# Module_DIO.net
KiCad netlist of a schematic drawn in EAGLE
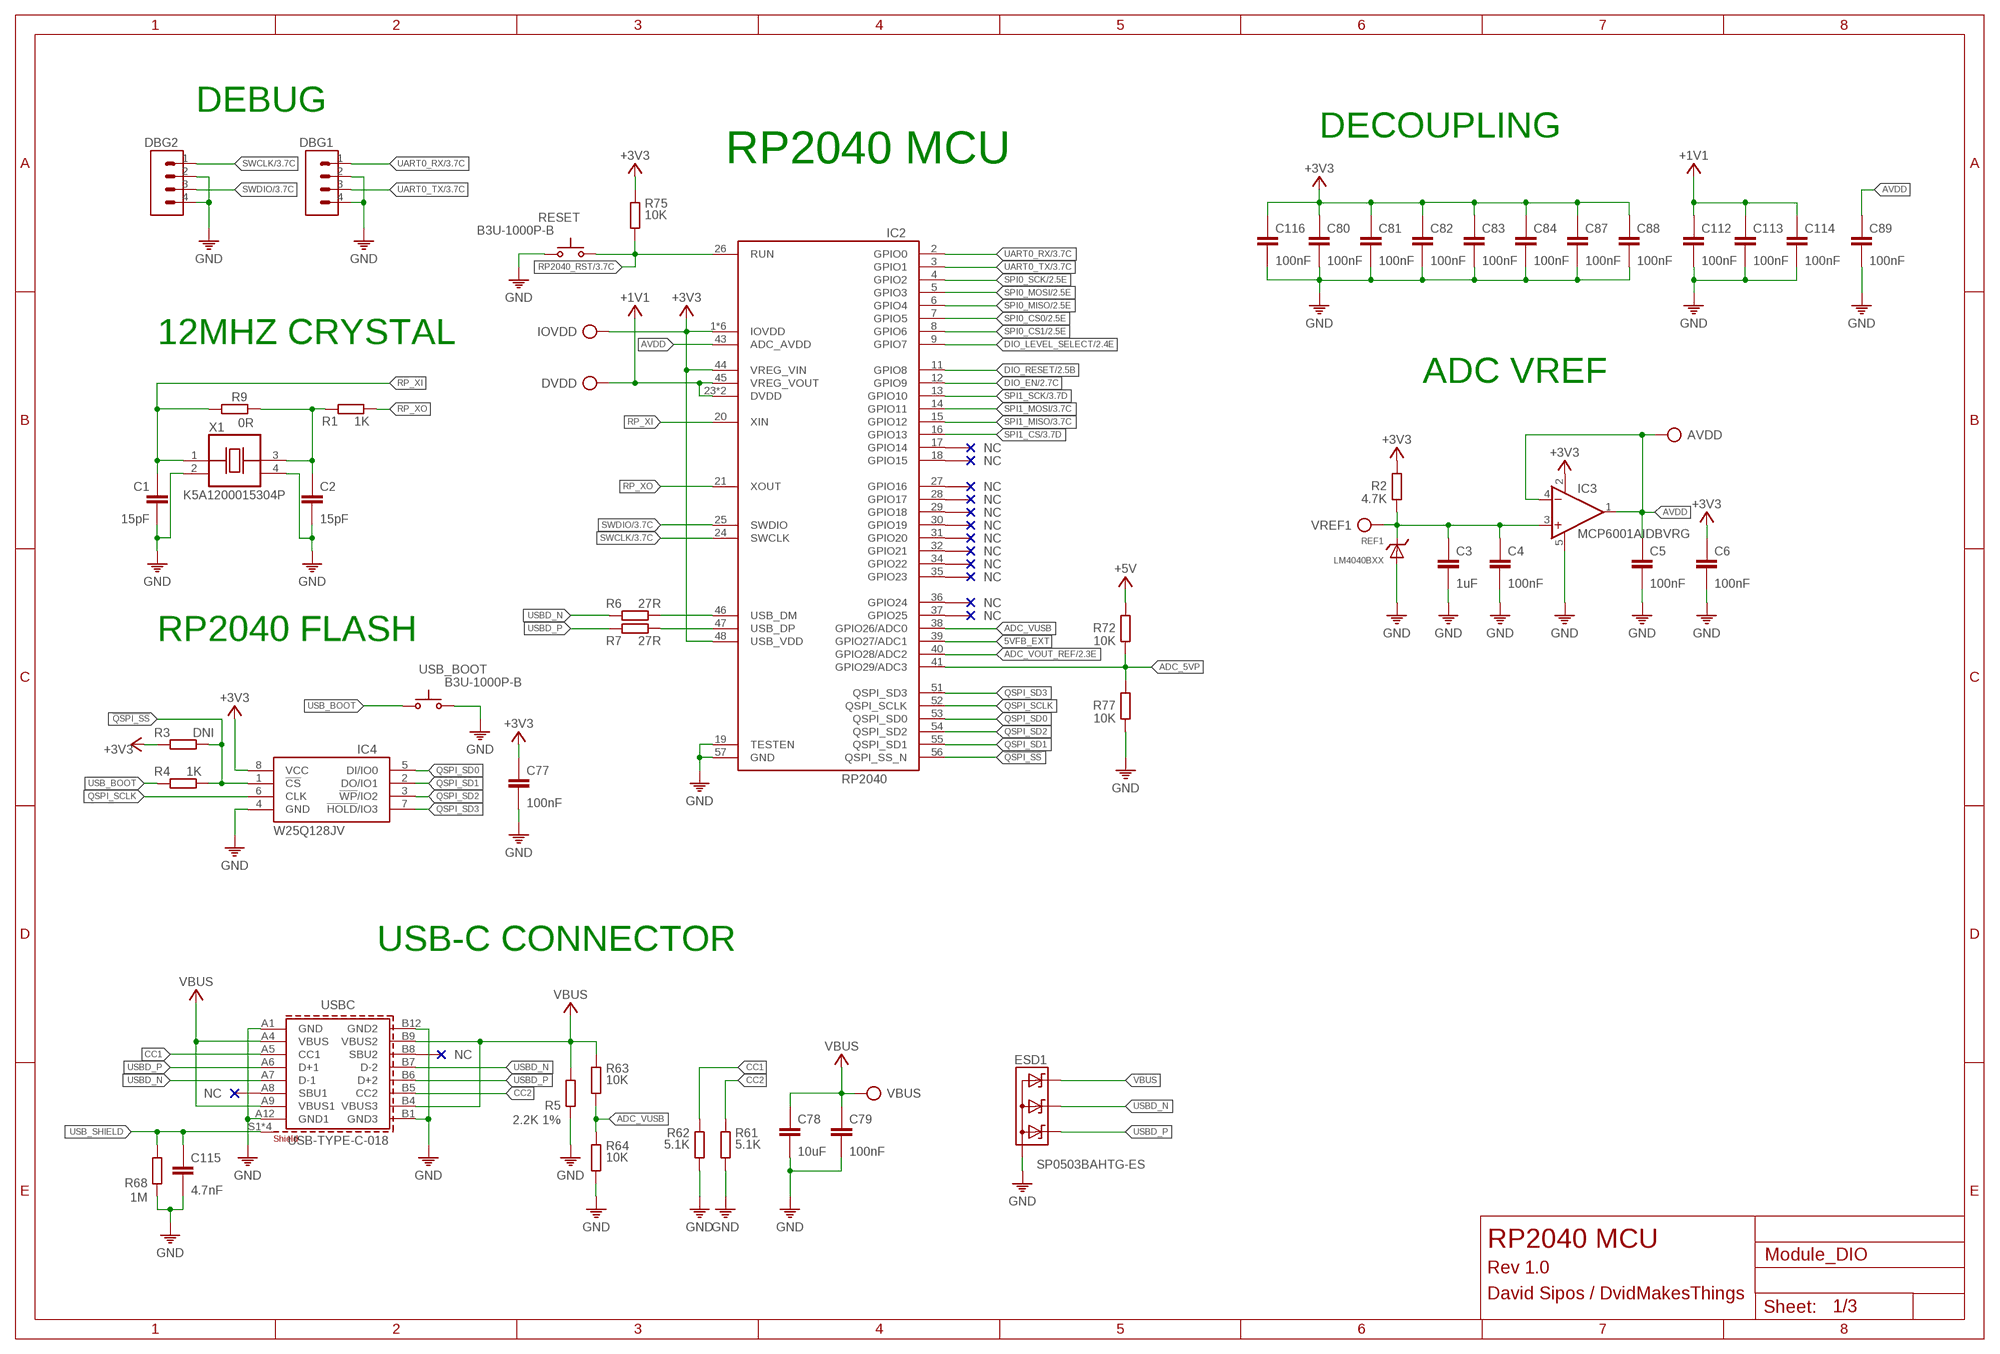
[diagram p0: schematic, sheet 1]
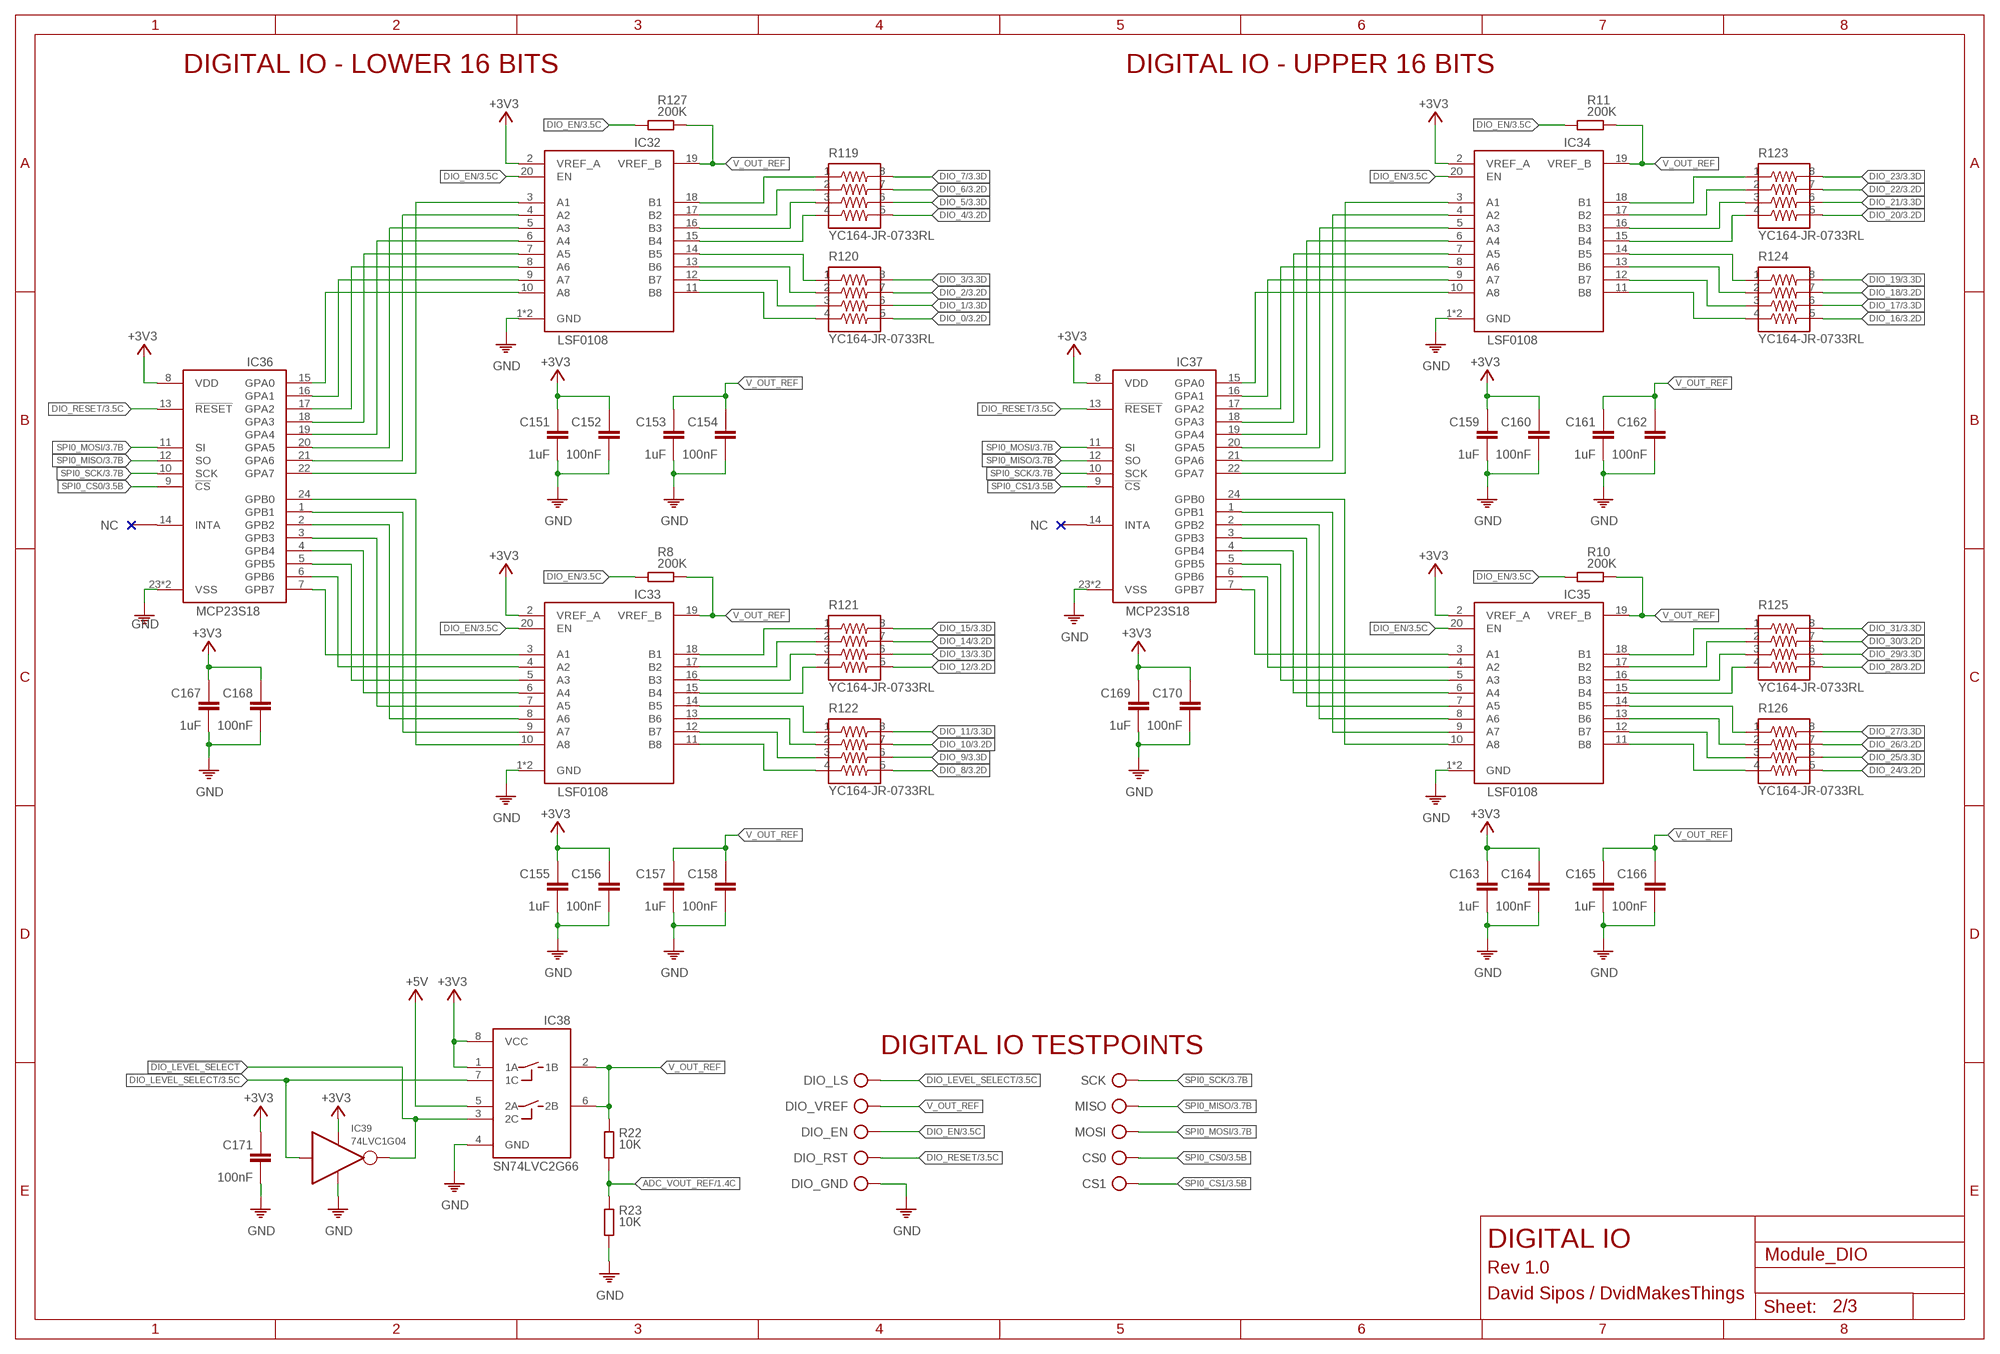
[diagram p1: schematic, sheet 2]
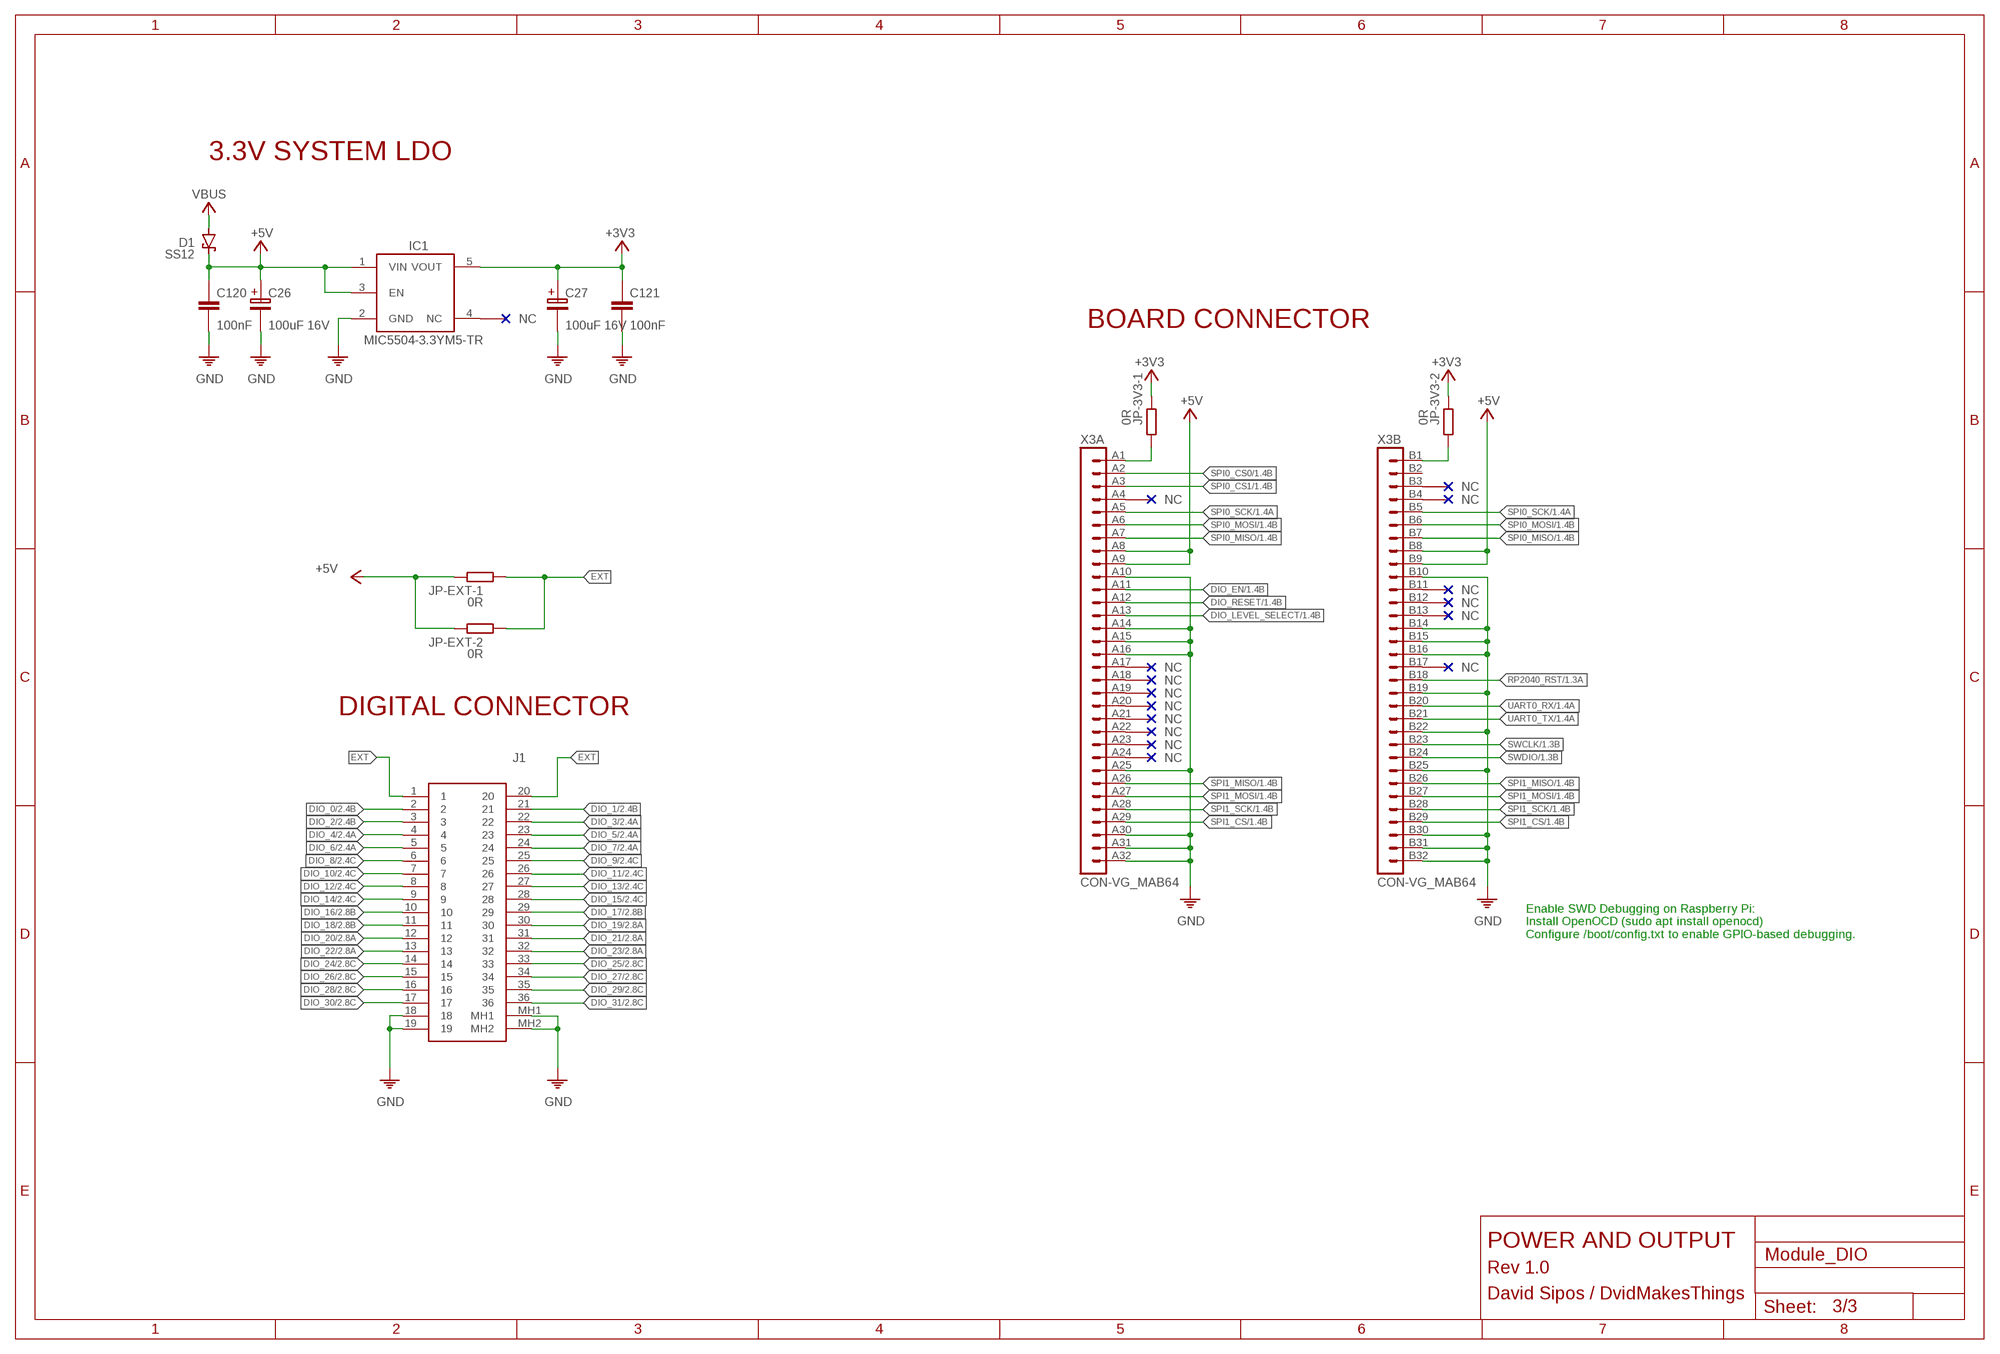
[diagram p2: schematic, sheet 3]

(export (version "E")
  (design (tool "Eeschema 10.0.6"))
  (components
    (comp (ref "AVDD")
      (value "TP")
      (footprint "eagle-import:TP")
      (libsource (lib "eagle-import") (part "TP"))
    )
    (comp (ref "C1")
      (value "15pF")
      (footprint "eagle-import:C0402")
      (libsource (lib "eagle-import") (part "C-0402"))
    )
    (comp (ref "C2")
      (value "15pF")
      (footprint "eagle-import:C0402")
      (libsource (lib "eagle-import") (part "C-0402"))
    )
    (comp (ref "C3")
      (value "1uF")
      (footprint "eagle-import:C0402")
      (libsource (lib "eagle-import") (part "C-0402"))
    )
    (comp (ref "C4")
      (value "100nF")
      (footprint "eagle-import:C0402")
      (libsource (lib "eagle-import") (part "C-0402"))
    )
    (comp (ref "C5")
      (value "100nF")
      (footprint "eagle-import:C0402")
      (libsource (lib "eagle-import") (part "C-0402"))
    )
    (comp (ref "C6")
      (value "100nF")
      (footprint "eagle-import:C0402")
      (libsource (lib "eagle-import") (part "C-0402"))
    )
    (comp (ref "C77")
      (value "100nF")
      (footprint "eagle-import:C0402")
      (libsource (lib "eagle-import") (part "C-0402"))
    )
    (comp (ref "C78")
      (value "10uF")
      (footprint "eagle-import:0805")
      (libsource (lib "eagle-import") (part "C0805"))
    )
    (comp (ref "C79")
      (value "100nF")
      (footprint "eagle-import:0402")
      (libsource (lib "eagle-import") (part "C0402"))
    )
    (comp (ref "C80")
      (value "100nF")
      (footprint "eagle-import:C0402")
      (libsource (lib "eagle-import") (part "C-0402"))
    )
    (comp (ref "C81")
      (value "100nF")
      (footprint "eagle-import:C0402")
      (libsource (lib "eagle-import") (part "C-0402"))
    )
    (comp (ref "C82")
      (value "100nF")
      (footprint "eagle-import:C0402")
      (libsource (lib "eagle-import") (part "C-0402"))
    )
    (comp (ref "C83")
      (value "100nF")
      (footprint "eagle-import:C0402")
      (libsource (lib "eagle-import") (part "C-0402"))
    )
    (comp (ref "C84")
      (value "100nF")
      (footprint "eagle-import:C0402")
      (libsource (lib "eagle-import") (part "C-0402"))
    )
    (comp (ref "C87")
      (value "100nF")
      (footprint "eagle-import:C0402")
      (libsource (lib "eagle-import") (part "C-0402"))
    )
    (comp (ref "C88")
      (value "100nF")
      (footprint "eagle-import:C0402")
      (libsource (lib "eagle-import") (part "C-0402"))
    )
    (comp (ref "C89")
      (value "100nF")
      (footprint "eagle-import:C0402")
      (libsource (lib "eagle-import") (part "C-0402"))
    )
    (comp (ref "C112")
      (value "100nF")
      (footprint "eagle-import:C0402")
      (libsource (lib "eagle-import") (part "C-0402"))
    )
    (comp (ref "C113")
      (value "100nF")
      (footprint "eagle-import:C0402")
      (libsource (lib "eagle-import") (part "C-0402"))
    )
    (comp (ref "C114")
      (value "100nF")
      (footprint "eagle-import:C0402")
      (libsource (lib "eagle-import") (part "C-0402"))
    )
    (comp (ref "C115")
      (value "4.7nF")
      (footprint "eagle-import:0402")
      (libsource (lib "eagle-import") (part "C0402"))
    )
    (comp (ref "C116")
      (value "100nF")
      (footprint "eagle-import:C0402")
      (libsource (lib "eagle-import") (part "C-0402"))
    )
    (comp (ref "DBG1")
      (value "CON-1X4")
      (footprint "eagle-import:1X4")
      (libsource (lib "eagle-import") (part "CON-1X4"))
    )
    (comp (ref "DBG2")
      (value "CON-1X4")
      (footprint "eagle-import:1X4")
      (libsource (lib "eagle-import") (part "CON-1X4"))
    )
    (comp (ref "DVDD")
      (value "TP")
      (footprint "eagle-import:TP")
      (libsource (lib "eagle-import") (part "TP"))
    )
    (comp (ref "ESD1")
      (value "SP0503BAHTG-ES")
      (footprint "eagle-import:SOT143")
      (libsource (lib "eagle-import") (part "SP0503BAHT"))
    )
    (comp (ref "IC2")
      (value "RP2040")
      (footprint "eagle-import:QFN40P700X700X100-57T510")
      (libsource (lib "eagle-import") (part "RP2040"))
    )
    (comp (ref "IC3")
      (value "MCP6001AIDBVRG")
      (footprint "eagle-import:SOT23-5")
      (libsource (lib "eagle-import") (part "MCP6001RT"))
    )
    (comp (ref "IC4")
      (value "W25Q128JVPIQ")
      (footprint "eagle-import:SON127P600X500X75-8N")
      (libsource (lib "eagle-import") (part "W25Q128JVP"))
    )
    (comp (ref "IOVDD")
      (value "TP")
      (footprint "eagle-import:TP")
      (libsource (lib "eagle-import") (part "TP"))
    )
    (comp (ref "R1")
      (value "1K")
      (footprint "eagle-import:0402")
      (libsource (lib "eagle-import") (part "R0402"))
    )
    (comp (ref "R2")
      (value "4.7K")
      (footprint "eagle-import:0402")
      (libsource (lib "eagle-import") (part "R0402"))
    )
    (comp (ref "R3")
      (value "DNI")
      (footprint "eagle-import:0402")
      (libsource (lib "eagle-import") (part "R0402"))
    )
    (comp (ref "R4")
      (value "1K")
      (footprint "eagle-import:0402")
      (libsource (lib "eagle-import") (part "R0402"))
    )
    (comp (ref "R5")
      (value "2.2K 1%")
      (footprint "eagle-import:0402")
      (libsource (lib "eagle-import") (part "ds_passive_46685041_R0402"))
    )
    (comp (ref "R6")
      (value "27R")
      (footprint "eagle-import:0402")
      (libsource (lib "eagle-import") (part "R0402"))
    )
    (comp (ref "R7")
      (value "27R")
      (footprint "eagle-import:0402")
      (libsource (lib "eagle-import") (part "R0402"))
    )
    (comp (ref "R9")
      (value "0R")
      (footprint "eagle-import:0402")
      (libsource (lib "eagle-import") (part "R0402"))
    )
    (comp (ref "R61")
      (value "5.1K")
      (footprint "eagle-import:0402")
      (libsource (lib "eagle-import") (part "ds_passive_46685041_R0402"))
    )
    (comp (ref "R62")
      (value "5.1K")
      (footprint "eagle-import:0402")
      (libsource (lib "eagle-import") (part "ds_passive_46685041_R0402"))
    )
    (comp (ref "R63")
      (value "10K")
      (footprint "eagle-import:0402")
      (libsource (lib "eagle-import") (part "ds_passive_46685041_R0402"))
    )
    (comp (ref "R64")
      (value "10K")
      (footprint "eagle-import:0402")
      (libsource (lib "eagle-import") (part "ds_passive_46685041_R0402"))
    )
    (comp (ref "R68")
      (value "1M")
      (footprint "eagle-import:0402")
      (libsource (lib "eagle-import") (part "ds_passive_46685041_R0402"))
    )
    (comp (ref "R72")
      (value "10K")
      (footprint "eagle-import:0402")
      (libsource (lib "eagle-import") (part "R0402"))
    )
    (comp (ref "R75")
      (value "10K")
      (footprint "eagle-import:0402")
      (libsource (lib "eagle-import") (part "ds_passive_46685041_R0402"))
    )
    (comp (ref "R77")
      (value "10K")
      (footprint "eagle-import:0402")
      (libsource (lib "eagle-import") (part "R0402"))
    )
    (comp (ref "REF1")
      (value "LM4040BXX")
      (footprint "eagle-import:SOT23")
      (libsource (lib "eagle-import") (part "LM4040BXX"))
    )
    (comp (ref "RESET")
      (value "B3U-1000P-B")
      (footprint "eagle-import:SWITCH-OMRON_B3U-1000P")
      (libsource (lib "eagle-import") (part "SWITCH-OMRON_B3U-1000P"))
    )
    (comp (ref "USBC")
      (value "USB-TYPE-C-018")
      (footprint "eagle-import:629722000214")
      (libsource (lib "eagle-import") (part "629722000214"))
    )
    (comp (ref "USB_BOOT")
      (value "B3U-1000P-B")
      (footprint "eagle-import:SWITCH-OMRON_B3U-1000P")
      (libsource (lib "eagle-import") (part "SWITCH-OMRON_B3U-1000P"))
    )
    (comp (ref "VBUS")
      (value "TP")
      (footprint "eagle-import:TP")
      (libsource (lib "eagle-import") (part "TP"))
    )
    (comp (ref "VREF1")
      (value "TP")
      (footprint "eagle-import:TP")
      (libsource (lib "eagle-import") (part "TP"))
    )
    (comp (ref "X1")
      (value "K5A1200015304P")
      (footprint "eagle-import:OSCCC500X320X130")
      (libsource (lib "eagle-import") (part "CRYSTAL"))
    )
    (comp (ref "C26")
      (value "100uF 16V")
      (footprint "eagle-import:100UF-16V")
      (libsource (lib "eagle-import") (part "CPOL"))
    )
    (comp (ref "C27")
      (value "100uF 16V")
      (footprint "eagle-import:100UF-16V")
      (libsource (lib "eagle-import") (part "CPOL"))
    )
    (comp (ref "C120")
      (value "100nF")
      (footprint "eagle-import:C0402")
      (libsource (lib "eagle-import") (part "C-0402"))
    )
    (comp (ref "C121")
      (value "100nF")
      (footprint "eagle-import:C0402")
      (libsource (lib "eagle-import") (part "C-0402"))
    )
    (comp (ref "D1")
      (value "SS12")
      (footprint "eagle-import:SMA")
      (fields
        (field (name "DIGIKEY_PART_NUMBER") "SS12FSCT-ND")
        (field (name "MANUFACTURER") "ON Semiconductor")
        (field (name "CREATED_BY") "PCBLayout.com")
      )
      (libsource (lib "eagle-import") (part "SS12"))
    )
    (comp (ref "IC1")
      (value "MIC5504-3.3YM5-TR")
      (footprint "eagle-import:SOT23-5")
      (libsource (lib "eagle-import") (part "MIC5504-3.3YM5-TR"))
    )
    (comp (ref "J1")
      (value "N10236-52B3PC")
      (footprint "eagle-import:MDB36")
      (libsource (lib "eagle-import") (part "N10236-52B3PC"))
    )
    (comp (ref "JP-3V3-1")
      (value "0R")
      (footprint "eagle-import:0603")
      (libsource (lib "eagle-import") (part "R0603"))
    )
    (comp (ref "JP-3V3-2")
      (value "0R")
      (footprint "eagle-import:0603")
      (libsource (lib "eagle-import") (part "R0603"))
    )
    (comp (ref "JP-EXT-1")
      (value "0R")
      (footprint "eagle-import:0603")
      (libsource (lib "eagle-import") (part "R0603"))
    )
    (comp (ref "JP-EXT-2")
      (value "0R")
      (footprint "eagle-import:0603")
      (libsource (lib "eagle-import") (part "R0603"))
    )
    (comp (ref "X3")
      (value "CON-VG_MAB64")
      (footprint "eagle-import:CON-VG_MAB64")
      (libsource (lib "eagle-import") (part "CON-VG_MAB64"))
    )
    (comp (ref "C151")
      (value "1uF")
      (footprint "eagle-import:C0402")
      (libsource (lib "eagle-import") (part "C-0402"))
    )
    (comp (ref "C152")
      (value "100nF")
      (footprint "eagle-import:C0402")
      (libsource (lib "eagle-import") (part "C-0402"))
    )
    (comp (ref "C153")
      (value "1uF")
      (footprint "eagle-import:C0402")
      (libsource (lib "eagle-import") (part "C-0402"))
    )
    (comp (ref "C154")
      (value "100nF")
      (footprint "eagle-import:C0402")
      (libsource (lib "eagle-import") (part "C-0402"))
    )
    (comp (ref "C155")
      (value "1uF")
      (footprint "eagle-import:C0402")
      (libsource (lib "eagle-import") (part "C-0402"))
    )
    (comp (ref "C156")
      (value "100nF")
      (footprint "eagle-import:C0402")
      (libsource (lib "eagle-import") (part "C-0402"))
    )
    (comp (ref "C157")
      (value "1uF")
      (footprint "eagle-import:C0402")
      (libsource (lib "eagle-import") (part "C-0402"))
    )
    (comp (ref "C158")
      (value "100nF")
      (footprint "eagle-import:C0402")
      (libsource (lib "eagle-import") (part "C-0402"))
    )
    (comp (ref "C159")
      (value "1uF")
      (footprint "eagle-import:C0402")
      (libsource (lib "eagle-import") (part "C-0402"))
    )
    (comp (ref "C160")
      (value "100nF")
      (footprint "eagle-import:C0402")
      (libsource (lib "eagle-import") (part "C-0402"))
    )
    (comp (ref "C161")
      (value "1uF")
      (footprint "eagle-import:C0402")
      (libsource (lib "eagle-import") (part "C-0402"))
    )
    (comp (ref "C162")
      (value "100nF")
      (footprint "eagle-import:C0402")
      (libsource (lib "eagle-import") (part "C-0402"))
    )
    (comp (ref "C163")
      (value "1uF")
      (footprint "eagle-import:C0402")
      (libsource (lib "eagle-import") (part "C-0402"))
    )
    (comp (ref "C164")
      (value "100nF")
      (footprint "eagle-import:C0402")
      (libsource (lib "eagle-import") (part "C-0402"))
    )
    (comp (ref "C165")
      (value "1uF")
      (footprint "eagle-import:C0402")
      (libsource (lib "eagle-import") (part "C-0402"))
    )
    (comp (ref "C166")
      (value "100nF")
      (footprint "eagle-import:C0402")
      (libsource (lib "eagle-import") (part "C-0402"))
    )
    (comp (ref "C167")
      (value "1uF")
      (footprint "eagle-import:C0402")
      (libsource (lib "eagle-import") (part "C-0402"))
    )
    (comp (ref "C168")
      (value "100nF")
      (footprint "eagle-import:C0402")
      (libsource (lib "eagle-import") (part "C-0402"))
    )
    (comp (ref "C169")
      (value "1uF")
      (footprint "eagle-import:C0402")
      (libsource (lib "eagle-import") (part "C-0402"))
    )
    (comp (ref "C170")
      (value "100nF")
      (footprint "eagle-import:C0402")
      (libsource (lib "eagle-import") (part "C-0402"))
    )
    (comp (ref "C171")
      (value "100nF")
      (footprint "eagle-import:C0603")
      (libsource (lib "eagle-import") (part "C-0603"))
    )
    (comp (ref "CS0") (value "TP") (footprint "eagle-import:TP") (libsource (lib "eagle-import") (part "TP")))
    (comp (ref "CS1") (value "TP") (footprint "eagle-import:TP") (libsource (lib "eagle-import") (part "TP")))
    (comp (ref "DIO_EN")
      (value "TP")
      (footprint "eagle-import:TP")
      (libsource (lib "eagle-import") (part "TP"))
    )
    (comp (ref "DIO_GND")
      (value "TP")
      (footprint "eagle-import:TP")
      (libsource (lib "eagle-import") (part "TP"))
    )
    (comp (ref "DIO_LS")
      (value "TP")
      (footprint "eagle-import:TP")
      (libsource (lib "eagle-import") (part "TP"))
    )
    (comp (ref "DIO_RST")
      (value "TP")
      (footprint "eagle-import:TP")
      (libsource (lib "eagle-import") (part "TP"))
    )
    (comp (ref "DIO_VREF")
      (value "TP")
      (footprint "eagle-import:TP")
      (libsource (lib "eagle-import") (part "TP"))
    )
    (comp (ref "IC32")
      (value "LSF0108")
      (footprint "eagle-import:VQFN20")
      (libsource (lib "eagle-import") (part "LSF0108-Q1"))
    )
    (comp (ref "IC33")
      (value "LSF0108")
      (footprint "eagle-import:VQFN20")
      (libsource (lib "eagle-import") (part "LSF0108-Q1"))
    )
    (comp (ref "IC34")
      (value "LSF0108")
      (footprint "eagle-import:VQFN20")
      (libsource (lib "eagle-import") (part "LSF0108-Q1"))
    )
    (comp (ref "IC35")
      (value "LSF0108")
      (footprint "eagle-import:VQFN20")
      (libsource (lib "eagle-import") (part "LSF0108-Q1"))
    )
    (comp (ref "IC36")
      (value "MCP23S18")
      (footprint "eagle-import:QFN50P400X400X100-25T265")
      (libsource (lib "eagle-import") (part "MCP23S18"))
    )
    (comp (ref "IC37")
      (value "MCP23S18")
      (footprint "eagle-import:QFN50P400X400X100-25T265")
      (libsource (lib "eagle-import") (part "MCP23S18"))
    )
    (comp (ref "IC38")
      (value "SN74LVC2G66")
      (footprint "eagle-import:SOP50P310X90-8N")
      (libsource (lib "eagle-import") (part "SN74LVC2G66"))
    )
    (comp (ref "IC39")
      (value "74LVC1G04")
      (footprint "eagle-import:SOT95P280X145-5N")
      (libsource (lib "eagle-import") (part "74LVC1G04"))
    )
    (comp (ref "MISO")
      (value "TP")
      (footprint "eagle-import:TP")
      (libsource (lib "eagle-import") (part "TP"))
    )
    (comp (ref "MOSI")
      (value "TP")
      (footprint "eagle-import:TP")
      (libsource (lib "eagle-import") (part "TP"))
    )
    (comp (ref "R8")
      (value "200K")
      (footprint "eagle-import:0402")
      (libsource (lib "eagle-import") (part "R0402"))
    )
    (comp (ref "R10")
      (value "200K")
      (footprint "eagle-import:0402")
      (libsource (lib "eagle-import") (part "R0402"))
    )
    (comp (ref "R11")
      (value "200K")
      (footprint "eagle-import:0402")
      (libsource (lib "eagle-import") (part "R0402"))
    )
    (comp (ref "R22")
      (value "10K")
      (footprint "eagle-import:0402")
      (libsource (lib "eagle-import") (part "R0402"))
    )
    (comp (ref "R23")
      (value "10K")
      (footprint "eagle-import:0402")
      (libsource (lib "eagle-import") (part "R0402"))
    )
    (comp (ref "R119")
      (value "YC164-JR-0733RL")
      (footprint "eagle-import:YC164-JR-0733RL")
      (fields (field (name "MANUFACTURER") "Yageo") (field (name "CREATED_BY") "PCBLayout.com"))
      (libsource (lib "eagle-import") (part "YC164-JR-0733RL"))
    )
    (comp (ref "R120")
      (value "YC164-JR-0733RL")
      (footprint "eagle-import:YC164-JR-0733RL")
      (fields (field (name "MANUFACTURER") "Yageo") (field (name "CREATED_BY") "PCBLayout.com"))
      (libsource (lib "eagle-import") (part "YC164-JR-0733RL"))
    )
    (comp (ref "R121")
      (value "YC164-JR-0733RL")
      (footprint "eagle-import:YC164-JR-0733RL")
      (fields (field (name "MANUFACTURER") "Yageo") (field (name "CREATED_BY") "PCBLayout.com"))
      (libsource (lib "eagle-import") (part "YC164-JR-0733RL"))
    )
    (comp (ref "R122")
      (value "YC164-JR-0733RL")
      (footprint "eagle-import:YC164-JR-0733RL")
      (fields (field (name "MANUFACTURER") "Yageo") (field (name "CREATED_BY") "PCBLayout.com"))
      (libsource (lib "eagle-import") (part "YC164-JR-0733RL"))
    )
    (comp (ref "R123")
      (value "YC164-JR-0733RL")
      (footprint "eagle-import:YC164-JR-0733RL")
      (fields (field (name "MANUFACTURER") "Yageo") (field (name "CREATED_BY") "PCBLayout.com"))
      (libsource (lib "eagle-import") (part "YC164-JR-0733RL"))
    )
    (comp (ref "R124")
      (value "YC164-JR-0733RL")
      (footprint "eagle-import:YC164-JR-0733RL")
      (fields (field (name "MANUFACTURER") "Yageo") (field (name "CREATED_BY") "PCBLayout.com"))
      (libsource (lib "eagle-import") (part "YC164-JR-0733RL"))
    )
    (comp (ref "R125")
      (value "YC164-JR-0733RL")
      (footprint "eagle-import:YC164-JR-0733RL")
      (fields (field (name "MANUFACTURER") "Yageo") (field (name "CREATED_BY") "PCBLayout.com"))
      (libsource (lib "eagle-import") (part "YC164-JR-0733RL"))
    )
    (comp (ref "R126")
      (value "YC164-JR-0733RL")
      (footprint "eagle-import:YC164-JR-0733RL")
      (fields (field (name "MANUFACTURER") "Yageo") (field (name "CREATED_BY") "PCBLayout.com"))
      (libsource (lib "eagle-import") (part "YC164-JR-0733RL"))
    )
    (comp (ref "R127")
      (value "200K")
      (footprint "eagle-import:0402")
      (libsource (lib "eagle-import") (part "R0402"))
    )
    (comp (ref "SCK") (value "TP") (footprint "eagle-import:TP") (libsource (lib "eagle-import") (part "TP")))
  )
  (nets
    (net (code "1") (name "+1V1") (class "Default")
      (node (ref "C112") (pin "1") (pinfunction "1_1") (pintype "passive"))
      (node (ref "C113") (pin "1") (pinfunction "1_1") (pintype "passive"))
      (node (ref "C114") (pin "1") (pinfunction "1_1") (pintype "passive"))
      (node (ref "DVDD") (pin "TP") (pinfunction "P$1_TP") (pintype "bidirectional"))
      (node (ref "IC2") (pin "23") (pinfunction "DVDD_23") (pintype "bidirectional"))
      (node (ref "IC2") (pin "45") (pinfunction "VREG_VOUT_45") (pintype "bidirectional"))
      (node (ref "IC2") (pin "50") (pinfunction "DVDD_50") (pintype "bidirectional"))
    )
    (net (code "2") (name "+3V3") (class "Default")
      (node (ref "C116") (pin "1") (pinfunction "1_1") (pintype "passive"))
      (node (ref "C121") (pin "1") (pinfunction "1_1") (pintype "passive"))
      (node (ref "C151") (pin "1") (pinfunction "1_1") (pintype "passive"))
      (node (ref "C152") (pin "1") (pinfunction "1_1") (pintype "passive"))
      (node (ref "C155") (pin "1") (pinfunction "1_1") (pintype "passive"))
      (node (ref "C156") (pin "1") (pinfunction "1_1") (pintype "passive"))
      (node (ref "C159") (pin "1") (pinfunction "1_1") (pintype "passive"))
      (node (ref "C160") (pin "1") (pinfunction "1_1") (pintype "passive"))
      (node (ref "C163") (pin "1") (pinfunction "1_1") (pintype "passive"))
      (node (ref "C164") (pin "1") (pinfunction "1_1") (pintype "passive"))
      (node (ref "C167") (pin "1") (pinfunction "1_1") (pintype "passive"))
      (node (ref "C168") (pin "1") (pinfunction "1_1") (pintype "passive"))
      (node (ref "C169") (pin "1") (pinfunction "1_1") (pintype "passive"))
      (node (ref "C170") (pin "1") (pinfunction "1_1") (pintype "passive"))
      (node (ref "C171") (pin "1") (pinfunction "1_1") (pintype "passive"))
      (node (ref "C27") (pin "1") (pinfunction "1_1") (pintype "passive"))
      (node (ref "C6") (pin "1") (pinfunction "1_1") (pintype "passive"))
      (node (ref "C77") (pin "1") (pinfunction "1_1") (pintype "passive"))
      (node (ref "C80") (pin "1") (pinfunction "1_1") (pintype "passive"))
      (node (ref "C81") (pin "1") (pinfunction "1_1") (pintype "passive"))
      (node (ref "C82") (pin "1") (pinfunction "1_1") (pintype "passive"))
      (node (ref "C83") (pin "1") (pinfunction "1_1") (pintype "passive"))
      (node (ref "C84") (pin "1") (pinfunction "1_1") (pintype "passive"))
      (node (ref "C87") (pin "1") (pinfunction "1_1") (pintype "passive"))
      (node (ref "C88") (pin "1") (pinfunction "1_1") (pintype "passive"))
      (node (ref "IC1") (pin "5") (pinfunction "VOUT_5") (pintype "bidirectional"))
      (node (ref "IC2") (pin "1") (pinfunction "IOVDD_1") (pintype "bidirectional"))
      (node (ref "IC2") (pin "10") (pinfunction "IOVDD_10") (pintype "bidirectional"))
      (node (ref "IC2") (pin "22") (pinfunction "IOVDD_22") (pintype "bidirectional"))
      (node (ref "IC2") (pin "33") (pinfunction "IOVDD_33") (pintype "bidirectional"))
      (node (ref "IC2") (pin "42") (pinfunction "IOVDD_42") (pintype "bidirectional"))
      (node (ref "IC2") (pin "44") (pinfunction "VREG_VIN_44") (pintype "bidirectional"))
      (node (ref "IC2") (pin "48") (pinfunction "USB_VDD_48") (pintype "bidirectional"))
      (node (ref "IC2") (pin "49") (pinfunction "IOVDD_49") (pintype "bidirectional"))
      (node (ref "IC3") (pin "2") (pinfunction "V+_2") (pintype "power_in"))
      (node (ref "IC32") (pin "2") (pinfunction "VREF_A_2") (pintype "power_in"))
      (node (ref "IC33") (pin "2") (pinfunction "VREF_A_2") (pintype "power_in"))
      (node (ref "IC34") (pin "2") (pinfunction "VREF_A_2") (pintype "power_in"))
      (node (ref "IC35") (pin "2") (pinfunction "VREF_A_2") (pintype "power_in"))
      (node (ref "IC36") (pin "8") (pinfunction "VDD_8") (pintype "power_in"))
      (node (ref "IC37") (pin "8") (pinfunction "VDD_8") (pintype "power_in"))
      (node (ref "IC38") (pin "1") (pinfunction "1A_1") (pintype "bidirectional"))
      (node (ref "IC38") (pin "8") (pinfunction "VCC_8") (pintype "power_in"))
      (node (ref "IC39") (pin "5") (pinfunction "V+_5") (pintype "bidirectional"))
      (node (ref "IC4") (pin "8") (pinfunction "VCC_8") (pintype "power_in"))
      (node (ref "IOVDD") (pin "TP") (pinfunction "P$1_TP") (pintype "bidirectional"))
      (node (ref "JP-3V3-1") (pin "1") (pinfunction "1_1") (pintype "passive"))
      (node (ref "JP-3V3-2") (pin "1") (pinfunction "1_1") (pintype "passive"))
      (node (ref "R2") (pin "2") (pinfunction "2_2") (pintype "passive"))
      (node (ref "R3") (pin "2") (pinfunction "2_2") (pintype "passive"))
      (node (ref "R75") (pin "1") (pinfunction "1_1") (pintype "passive"))
    )
    (net (code "3") (name "+5V") (class "Default")
      (node (ref "C120") (pin "1") (pinfunction "1_1") (pintype "passive"))
      (node (ref "C26") (pin "1") (pinfunction "1_1") (pintype "passive"))
      (node (ref "D1") (pin "C") (pinfunction "C_C") (pintype "passive"))
      (node (ref "IC1") (pin "1") (pinfunction "VIN_1") (pintype "bidirectional"))
      (node (ref "IC1") (pin "3") (pinfunction "EN_3") (pintype "bidirectional"))
      (node (ref "IC38") (pin "5") (pinfunction "2A_5") (pintype "bidirectional"))
      (node (ref "JP-EXT-1") (pin "1") (pinfunction "1_1") (pintype "passive"))
      (node (ref "JP-EXT-2") (pin "1") (pinfunction "1_1") (pintype "passive"))
      (node (ref "R72") (pin "2") (pinfunction "2_2") (pintype "passive"))
      (node (ref "X3") (pin "A8") (pinfunction "8_A8") (pintype "passive"))
      (node (ref "X3") (pin "A9") (pinfunction "9_A9") (pintype "passive"))
      (node (ref "X3") (pin "B8") (pinfunction "8_B8") (pintype "passive"))
      (node (ref "X3") (pin "B9") (pinfunction "9_B9") (pintype "passive"))
    )
    (net (code "4") (name "5VFB_EXT") (class "Default")
      (node (ref "IC2") (pin "39") (pinfunction "GPIO27/ADC1_39") (pintype "bidirectional"))
    )
    (net (code "5") (name "ADC_5VP") (class "Default")
      (node (ref "IC2") (pin "41") (pinfunction "GPIO29/ADC3_41") (pintype "bidirectional"))
      (node (ref "R72") (pin "1") (pinfunction "1_1") (pintype "passive"))
      (node (ref "R77") (pin "2") (pinfunction "2_2") (pintype "passive"))
    )
    (net (code "6") (name "ADC_VOUT_REF") (class "Default")
      (node (ref "IC2") (pin "40") (pinfunction "GPIO28/ADC2_40") (pintype "bidirectional"))
      (node (ref "R22") (pin "2") (pinfunction "2_2") (pintype "passive"))
      (node (ref "R23") (pin "1") (pinfunction "1_1") (pintype "passive"))
    )
    (net (code "7") (name "ADC_VUSB") (class "Default")
      (node (ref "IC2") (pin "38") (pinfunction "GPIO26/ADC0_38") (pintype "bidirectional"))
      (node (ref "R63") (pin "2") (pinfunction "2_2") (pintype "passive"))
      (node (ref "R64") (pin "1") (pinfunction "1_1") (pintype "passive"))
    )
    (net (code "8") (name "AVDD") (class "Default")
      (node (ref "AVDD") (pin "TP") (pinfunction "P$1_TP") (pintype "bidirectional"))
      (node (ref "C5") (pin "1") (pinfunction "1_1") (pintype "passive"))
      (node (ref "C89") (pin "1") (pinfunction "1_1") (pintype "passive"))
      (node (ref "IC2") (pin "43") (pinfunction "ADC_AVDD_43") (pintype "bidirectional"))
      (node (ref "IC3") (pin "1") (pinfunction "OUT_1") (pintype "output"))
      (node (ref "IC3") (pin "4") (pinfunction "-IN_4") (pintype "input"))
    )
    (net (code "9") (name "CC1") (class "Default")
      (node (ref "R62") (pin "1") (pinfunction "1_1") (pintype "passive"))
      (node (ref "USBC") (pin "A5") (pinfunction "CC1_A5") (pintype "passive"))
    )
    (net (code "10") (name "CC2") (class "Default")
      (node (ref "R61") (pin "1") (pinfunction "1_1") (pintype "passive"))
      (node (ref "USBC") (pin "B5") (pinfunction "CC2_B5") (pintype "passive"))
    )
    (net (code "11") (name "DIO_0") (class "Default")
      (node (ref "J1") (pin "2") (pinfunction "2_2") (pintype "bidirectional"))
      (node (ref "R120") (pin "5") (pinfunction "5_5") (pintype "passive"))
    )
    (net (code "12") (name "DIO_1") (class "Default")
      (node (ref "J1") (pin "21") (pinfunction "21_21") (pintype "bidirectional"))
      (node (ref "R120") (pin "6") (pinfunction "6_6") (pintype "passive"))
    )
    (net (code "13") (name "DIO_2") (class "Default")
      (node (ref "J1") (pin "3") (pinfunction "3_3") (pintype "bidirectional"))
      (node (ref "R120") (pin "7") (pinfunction "7_7") (pintype "passive"))
    )
    (net (code "14") (name "DIO_3") (class "Default")
      (node (ref "J1") (pin "22") (pinfunction "22_22") (pintype "bidirectional"))
      (node (ref "R120") (pin "8") (pinfunction "8_8") (pintype "passive"))
    )
    (net (code "15") (name "DIO_4") (class "Default")
      (node (ref "J1") (pin "4") (pinfunction "4_4") (pintype "bidirectional"))
      (node (ref "R119") (pin "5") (pinfunction "5_5") (pintype "passive"))
    )
    (net (code "16") (name "DIO_5") (class "Default")
      (node (ref "J1") (pin "23") (pinfunction "23_23") (pintype "bidirectional"))
      (node (ref "R119") (pin "6") (pinfunction "6_6") (pintype "passive"))
    )
    (net (code "17") (name "DIO_6") (class "Default")
      (node (ref "J1") (pin "5") (pinfunction "5_5") (pintype "bidirectional"))
      (node (ref "R119") (pin "7") (pinfunction "7_7") (pintype "passive"))
    )
    (net (code "18") (name "DIO_7") (class "Default")
      (node (ref "J1") (pin "24") (pinfunction "24_24") (pintype "bidirectional"))
      (node (ref "R119") (pin "8") (pinfunction "8_8") (pintype "passive"))
    )
    (net (code "19") (name "DIO_8") (class "Default")
      (node (ref "J1") (pin "6") (pinfunction "6_6") (pintype "bidirectional"))
      (node (ref "R122") (pin "5") (pinfunction "5_5") (pintype "passive"))
    )
    (net (code "20") (name "DIO_9") (class "Default")
      (node (ref "J1") (pin "25") (pinfunction "25_25") (pintype "bidirectional"))
      (node (ref "R122") (pin "6") (pinfunction "6_6") (pintype "passive"))
    )
    (net (code "21") (name "DIO_10") (class "Default")
      (node (ref "J1") (pin "7") (pinfunction "7_7") (pintype "bidirectional"))
      (node (ref "R122") (pin "7") (pinfunction "7_7") (pintype "passive"))
    )
    (net (code "22") (name "DIO_11") (class "Default")
      (node (ref "J1") (pin "26") (pinfunction "26_26") (pintype "bidirectional"))
      (node (ref "R122") (pin "8") (pinfunction "8_8") (pintype "passive"))
    )
    (net (code "23") (name "DIO_12") (class "Default")
      (node (ref "J1") (pin "8") (pinfunction "8_8") (pintype "bidirectional"))
      (node (ref "R121") (pin "5") (pinfunction "5_5") (pintype "passive"))
    )
    (net (code "24") (name "DIO_13") (class "Default")
      (node (ref "J1") (pin "27") (pinfunction "27_27") (pintype "bidirectional"))
      (node (ref "R121") (pin "6") (pinfunction "6_6") (pintype "passive"))
    )
    (net (code "25") (name "DIO_14") (class "Default")
      (node (ref "J1") (pin "9") (pinfunction "9_9") (pintype "bidirectional"))
      (node (ref "R121") (pin "7") (pinfunction "7_7") (pintype "passive"))
    )
    (net (code "26") (name "DIO_15") (class "Default")
      (node (ref "J1") (pin "28") (pinfunction "28_28") (pintype "bidirectional"))
      (node (ref "R121") (pin "8") (pinfunction "8_8") (pintype "passive"))
    )
    (net (code "27") (name "DIO_16") (class "Default")
      (node (ref "J1") (pin "10") (pinfunction "10_10") (pintype "bidirectional"))
      (node (ref "R124") (pin "5") (pinfunction "5_5") (pintype "passive"))
    )
    (net (code "28") (name "DIO_17") (class "Default")
      (node (ref "J1") (pin "29") (pinfunction "29_29") (pintype "bidirectional"))
      (node (ref "R124") (pin "6") (pinfunction "6_6") (pintype "passive"))
    )
    (net (code "29") (name "DIO_18") (class "Default")
      (node (ref "J1") (pin "11") (pinfunction "11_11") (pintype "bidirectional"))
      (node (ref "R124") (pin "7") (pinfunction "7_7") (pintype "passive"))
    )
    (net (code "30") (name "DIO_19") (class "Default")
      (node (ref "J1") (pin "30") (pinfunction "30_30") (pintype "bidirectional"))
      (node (ref "R124") (pin "8") (pinfunction "8_8") (pintype "passive"))
    )
    (net (code "31") (name "DIO_20") (class "Default")
      (node (ref "J1") (pin "12") (pinfunction "12_12") (pintype "bidirectional"))
      (node (ref "R123") (pin "5") (pinfunction "5_5") (pintype "passive"))
    )
    (net (code "32") (name "DIO_21") (class "Default")
      (node (ref "J1") (pin "31") (pinfunction "31_31") (pintype "bidirectional"))
      (node (ref "R123") (pin "6") (pinfunction "6_6") (pintype "passive"))
    )
    (net (code "33") (name "DIO_22") (class "Default")
      (node (ref "J1") (pin "13") (pinfunction "13_13") (pintype "bidirectional"))
      (node (ref "R123") (pin "7") (pinfunction "7_7") (pintype "passive"))
    )
    (net (code "34") (name "DIO_23") (class "Default")
      (node (ref "J1") (pin "32") (pinfunction "32_32") (pintype "bidirectional"))
      (node (ref "R123") (pin "8") (pinfunction "8_8") (pintype "passive"))
    )
    (net (code "35") (name "DIO_24") (class "Default")
      (node (ref "J1") (pin "14") (pinfunction "14_14") (pintype "bidirectional"))
      (node (ref "R126") (pin "5") (pinfunction "5_5") (pintype "passive"))
    )
    (net (code "36") (name "DIO_25") (class "Default")
      (node (ref "J1") (pin "33") (pinfunction "33_33") (pintype "bidirectional"))
      (node (ref "R126") (pin "6") (pinfunction "6_6") (pintype "passive"))
    )
    (net (code "37") (name "DIO_26") (class "Default")
      (node (ref "J1") (pin "15") (pinfunction "15_15") (pintype "bidirectional"))
      (node (ref "R126") (pin "7") (pinfunction "7_7") (pintype "passive"))
    )
    (net (code "38") (name "DIO_27") (class "Default")
      (node (ref "J1") (pin "34") (pinfunction "34_34") (pintype "bidirectional"))
      (node (ref "R126") (pin "8") (pinfunction "8_8") (pintype "passive"))
    )
    (net (code "39") (name "DIO_28") (class "Default")
      (node (ref "J1") (pin "16") (pinfunction "16_16") (pintype "bidirectional"))
      (node (ref "R125") (pin "5") (pinfunction "5_5") (pintype "passive"))
    )
    (net (code "40") (name "DIO_29") (class "Default")
      (node (ref "J1") (pin "35") (pinfunction "35_35") (pintype "bidirectional"))
      (node (ref "R125") (pin "6") (pinfunction "6_6") (pintype "passive"))
    )
    (net (code "41") (name "DIO_30") (class "Default")
      (node (ref "J1") (pin "17") (pinfunction "17_17") (pintype "bidirectional"))
      (node (ref "R125") (pin "7") (pinfunction "7_7") (pintype "passive"))
    )
    (net (code "42") (name "DIO_31") (class "Default")
      (node (ref "J1") (pin "36") (pinfunction "36_36") (pintype "bidirectional"))
      (node (ref "R125") (pin "8") (pinfunction "8_8") (pintype "passive"))
    )
    (net (code "43") (name "DIO_EN") (class "Default")
      (node (ref "DIO_EN") (pin "TP") (pinfunction "P$1_TP") (pintype "bidirectional"))
      (node (ref "IC2") (pin "12") (pinfunction "GPIO9_12") (pintype "bidirectional"))
      (node (ref "IC32") (pin "20") (pinfunction "EN_20") (pintype "bidirectional"))
      (node (ref "IC33") (pin "20") (pinfunction "EN_20") (pintype "bidirectional"))
      (node (ref "IC34") (pin "20") (pinfunction "EN_20") (pintype "bidirectional"))
      (node (ref "IC35") (pin "20") (pinfunction "EN_20") (pintype "bidirectional"))
      (node (ref "R10") (pin "2") (pinfunction "2_2") (pintype "passive"))
      (node (ref "R11") (pin "2") (pinfunction "2_2") (pintype "passive"))
      (node (ref "R127") (pin "2") (pinfunction "2_2") (pintype "passive"))
      (node (ref "R8") (pin "2") (pinfunction "2_2") (pintype "passive"))
      (node (ref "X3") (pin "A11") (pinfunction "11_A11") (pintype "passive"))
    )
    (net (code "44") (name "DIO_LEVEL_SELECT") (class "Default")
      (node (ref "DIO_LS") (pin "TP") (pinfunction "P$1_TP") (pintype "bidirectional"))
      (node (ref "IC2") (pin "9") (pinfunction "GPIO7_9") (pintype "bidirectional"))
      (node (ref "IC38") (pin "7") (pinfunction "1C_7") (pintype "input"))
      (node (ref "IC39") (pin "2") (pinfunction "IN_2") (pintype "bidirectional"))
      (node (ref "X3") (pin "A13") (pinfunction "13_A13") (pintype "passive"))
    )
    (net (code "45") (name "DIO_RESET") (class "Default")
      (node (ref "DIO_RST") (pin "TP") (pinfunction "P$1_TP") (pintype "bidirectional"))
      (node (ref "IC2") (pin "11") (pinfunction "GPIO8_11") (pintype "bidirectional"))
      (node (ref "IC36") (pin "13") (pinfunction "~{RESET}_13") (pintype "input"))
      (node (ref "IC37") (pin "13") (pinfunction "~{RESET}_13") (pintype "input"))
      (node (ref "X3") (pin "A12") (pinfunction "12_A12") (pintype "passive"))
    )
    (net (code "46") (name "EXT") (class "Default")
      (node (ref "J1") (pin "1") (pinfunction "1_1") (pintype "bidirectional"))
      (node (ref "J1") (pin "20") (pinfunction "20_20") (pintype "bidirectional"))
      (node (ref "JP-EXT-1") (pin "2") (pinfunction "2_2") (pintype "passive"))
      (node (ref "JP-EXT-2") (pin "2") (pinfunction "2_2") (pintype "passive"))
    )
    (net (code "47") (name "GND") (class "Default")
      (node (ref "C1") (pin "2") (pinfunction "2_2") (pintype "passive"))
      (node (ref "C112") (pin "2") (pinfunction "2_2") (pintype "passive"))
      (node (ref "C113") (pin "2") (pinfunction "2_2") (pintype "passive"))
      (node (ref "C114") (pin "2") (pinfunction "2_2") (pintype "passive"))
      (node (ref "C115") (pin "2") (pinfunction "2_2") (pintype "passive"))
      (node (ref "C116") (pin "2") (pinfunction "2_2") (pintype "passive"))
      (node (ref "C120") (pin "2") (pinfunction "2_2") (pintype "passive"))
      (node (ref "C121") (pin "2") (pinfunction "2_2") (pintype "passive"))
      (node (ref "C151") (pin "2") (pinfunction "2_2") (pintype "passive"))
      (node (ref "C152") (pin "2") (pinfunction "2_2") (pintype "passive"))
      (node (ref "C153") (pin "2") (pinfunction "2_2") (pintype "passive"))
      (node (ref "C154") (pin "2") (pinfunction "2_2") (pintype "passive"))
      (node (ref "C155") (pin "2") (pinfunction "2_2") (pintype "passive"))
      (node (ref "C156") (pin "2") (pinfunction "2_2") (pintype "passive"))
      (node (ref "C157") (pin "2") (pinfunction "2_2") (pintype "passive"))
      (node (ref "C158") (pin "2") (pinfunction "2_2") (pintype "passive"))
      (node (ref "C159") (pin "2") (pinfunction "2_2") (pintype "passive"))
      (node (ref "C160") (pin "2") (pinfunction "2_2") (pintype "passive"))
      (node (ref "C161") (pin "2") (pinfunction "2_2") (pintype "passive"))
      (node (ref "C162") (pin "2") (pinfunction "2_2") (pintype "passive"))
      (node (ref "C163") (pin "2") (pinfunction "2_2") (pintype "passive"))
      (node (ref "C164") (pin "2") (pinfunction "2_2") (pintype "passive"))
      (node (ref "C165") (pin "2") (pinfunction "2_2") (pintype "passive"))
      (node (ref "C166") (pin "2") (pinfunction "2_2") (pintype "passive"))
      (node (ref "C167") (pin "2") (pinfunction "2_2") (pintype "passive"))
      (node (ref "C168") (pin "2") (pinfunction "2_2") (pintype "passive"))
      (node (ref "C169") (pin "2") (pinfunction "2_2") (pintype "passive"))
      (node (ref "C170") (pin "2") (pinfunction "2_2") (pintype "passive"))
      (node (ref "C171") (pin "2") (pinfunction "2_2") (pintype "passive"))
      (node (ref "C2") (pin "2") (pinfunction "2_2") (pintype "passive"))
      (node (ref "C26") (pin "2") (pinfunction "2_2") (pintype "passive"))
      (node (ref "C27") (pin "2") (pinfunction "2_2") (pintype "passive"))
      (node (ref "C3") (pin "2") (pinfunction "2_2") (pintype "passive"))
      (node (ref "C4") (pin "2") (pinfunction "2_2") (pintype "passive"))
      (node (ref "C5") (pin "2") (pinfunction "2_2") (pintype "passive"))
      (node (ref "C6") (pin "2") (pinfunction "2_2") (pintype "passive"))
      (node (ref "C77") (pin "2") (pinfunction "2_2") (pintype "passive"))
      (node (ref "C78") (pin "2") (pinfunction "2_2") (pintype "passive"))
      (node (ref "C79") (pin "2") (pinfunction "2_2") (pintype "passive"))
      (node (ref "C80") (pin "2") (pinfunction "2_2") (pintype "passive"))
      (node (ref "C81") (pin "2") (pinfunction "2_2") (pintype "passive"))
      (node (ref "C82") (pin "2") (pinfunction "2_2") (pintype "passive"))
      (node (ref "C83") (pin "2") (pinfunction "2_2") (pintype "passive"))
      (node (ref "C84") (pin "2") (pinfunction "2_2") (pintype "passive"))
      (node (ref "C87") (pin "2") (pinfunction "2_2") (pintype "passive"))
      (node (ref "C88") (pin "2") (pinfunction "2_2") (pintype "passive"))
      (node (ref "C89") (pin "2") (pinfunction "2_2") (pintype "passive"))
      (node (ref "DBG1") (pin "2") (pinfunction "P$2_2") (pintype "bidirectional"))
      (node (ref "DBG1") (pin "4") (pinfunction "P$4_4") (pintype "bidirectional"))
      (node (ref "DBG2") (pin "2") (pinfunction "P$2_2") (pintype "bidirectional"))
      (node (ref "DBG2") (pin "4") (pinfunction "P$4_4") (pintype "bidirectional"))
      (node (ref "DIO_GND") (pin "TP") (pinfunction "P$1_TP") (pintype "bidirectional"))
      (node (ref "ESD1") (pin "1") (pinfunction "A_1") (pintype "bidirectional"))
      (node (ref "IC1") (pin "2") (pinfunction "GND_2") (pintype "bidirectional"))
      (node (ref "IC2") (pin "19") (pinfunction "TESTEN_19") (pintype "bidirectional"))
      (node (ref "IC2") (pin "57") (pinfunction "GND_57") (pintype "bidirectional"))
      (node (ref "IC3") (pin "5") (pinfunction "V-_5") (pintype "power_in"))
      (node (ref "IC32") (pin "1") (pinfunction "GND_1") (pintype "power_in"))
      (node (ref "IC32") (pin "PAD") (pinfunction "GND_PAD") (pintype "power_in"))
      (node (ref "IC33") (pin "1") (pinfunction "GND_1") (pintype "power_in"))
      (node (ref "IC33") (pin "PAD") (pinfunction "GND_PAD") (pintype "power_in"))
      (node (ref "IC34") (pin "1") (pinfunction "GND_1") (pintype "power_in"))
      (node (ref "IC34") (pin "PAD") (pinfunction "GND_PAD") (pintype "power_in"))
      (node (ref "IC35") (pin "1") (pinfunction "GND_1") (pintype "power_in"))
      (node (ref "IC35") (pin "PAD") (pinfunction "GND_PAD") (pintype "power_in"))
      (node (ref "IC36") (pin "23") (pinfunction "VSS_23") (pintype "power_in"))
      (node (ref "IC36") (pin "25") (pinfunction "VSS_25") (pintype "power_in"))
      (node (ref "IC37") (pin "23") (pinfunction "VSS_23") (pintype "power_in"))
      (node (ref "IC37") (pin "25") (pinfunction "VSS_25") (pintype "power_in"))
      (node (ref "IC38") (pin "4") (pinfunction "GND_4") (pintype "power_in"))
      (node (ref "IC39") (pin "3") (pinfunction "V-_3") (pintype "bidirectional"))
      (node (ref "IC4") (pin "4") (pinfunction "GND_4") (pintype "power_in"))
      (node (ref "J1") (pin "18") (pinfunction "18_18") (pintype "bidirectional"))
      (node (ref "J1") (pin "19") (pinfunction "19_19") (pintype "bidirectional"))
      (node (ref "J1") (pin "MH1") (pinfunction "MH1_MH1") (pintype "bidirectional"))
      (node (ref "J1") (pin "MH2") (pinfunction "MH2_MH2") (pintype "bidirectional"))
      (node (ref "R23") (pin "2") (pinfunction "2_2") (pintype "passive"))
      (node (ref "R5") (pin "2") (pinfunction "2_2") (pintype "passive"))
      (node (ref "R61") (pin "2") (pinfunction "2_2") (pintype "passive"))
      (node (ref "R62") (pin "2") (pinfunction "2_2") (pintype "passive"))
      (node (ref "R64") (pin "2") (pinfunction "2_2") (pintype "passive"))
      (node (ref "R68") (pin "2") (pinfunction "2_2") (pintype "passive"))
      (node (ref "R77") (pin "1") (pinfunction "1_1") (pintype "passive"))
      (node (ref "REF1") (pin "2") (pinfunction "A_2") (pintype "passive"))
      (node (ref "REF1") (pin "3") (pinfunction "A_3") (pintype "passive"))
      (node (ref "RESET") (pin "2") (pinfunction "S_2") (pintype "passive"))
      (node (ref "USBC") (pin "A1") (pinfunction "GND_A1") (pintype "passive"))
      (node (ref "USBC") (pin "A12") (pinfunction "GND1_A12") (pintype "passive"))
      (node (ref "USBC") (pin "B1") (pinfunction "GND3_B1") (pintype "passive"))
      (node (ref "USBC") (pin "B12") (pinfunction "GND2_B12") (pintype "passive"))
      (node (ref "USB_BOOT") (pin "2") (pinfunction "S_2") (pintype "passive"))
      (node (ref "X1") (pin "2") (pinfunction "VSS_2") (pintype "power_in"))
      (node (ref "X1") (pin "4") (pinfunction "VDD_4") (pintype "power_in"))
      (node (ref "X3") (pin "A10") (pinfunction "10_A10") (pintype "passive"))
      (node (ref "X3") (pin "A14") (pinfunction "14_A14") (pintype "passive"))
      (node (ref "X3") (pin "A15") (pinfunction "15_A15") (pintype "passive"))
      (node (ref "X3") (pin "A16") (pinfunction "16_A16") (pintype "passive"))
      (node (ref "X3") (pin "A25") (pinfunction "25_A25") (pintype "passive"))
      (node (ref "X3") (pin "A30") (pinfunction "30_A30") (pintype "passive"))
      (node (ref "X3") (pin "A31") (pinfunction "31_A31") (pintype "passive"))
      (node (ref "X3") (pin "A32") (pinfunction "32_A32") (pintype "passive"))
      (node (ref "X3") (pin "B10") (pinfunction "10_B10") (pintype "passive"))
      (node (ref "X3") (pin "B14") (pinfunction "14_B14") (pintype "passive"))
      (node (ref "X3") (pin "B15") (pinfunction "15_B15") (pintype "passive"))
      (node (ref "X3") (pin "B16") (pinfunction "16_B16") (pintype "passive"))
      (node (ref "X3") (pin "B19") (pinfunction "19_B19") (pintype "passive"))
      (node (ref "X3") (pin "B22") (pinfunction "22_B22") (pintype "passive"))
      (node (ref "X3") (pin "B25") (pinfunction "25_B25") (pintype "passive"))
      (node (ref "X3") (pin "B30") (pinfunction "30_B30") (pintype "passive"))
      (node (ref "X3") (pin "B31") (pinfunction "31_B31") (pintype "passive"))
      (node (ref "X3") (pin "B32") (pinfunction "32_B32") (pintype "passive"))
    )
    (net (code "48") (name "Net-(IC2-USB_DM)") (class "Default")
      (node (ref "IC2") (pin "46") (pinfunction "USB_DM_46") (pintype "bidirectional"))
      (node (ref "R6") (pin "2") (pinfunction "2_2") (pintype "passive"))
    )
    (net (code "49") (name "Net-(IC2-USB_DP)") (class "Default")
      (node (ref "IC2") (pin "47") (pinfunction "USB_DP_47") (pintype "bidirectional"))
      (node (ref "R7") (pin "2") (pinfunction "2_2") (pintype "passive"))
    )
    (net (code "50") (name "Net-(IC3-+IN)") (class "Default")
      (node (ref "C3") (pin "1") (pinfunction "1_1") (pintype "passive"))
      (node (ref "C4") (pin "1") (pinfunction "1_1") (pintype "passive"))
      (node (ref "IC3") (pin "3") (pinfunction "+IN_3") (pintype "input"))
      (node (ref "R2") (pin "1") (pinfunction "1_1") (pintype "passive"))
      (node (ref "REF1") (pin "1") (pinfunction "C_1") (pintype "passive"))
      (node (ref "VREF1") (pin "TP") (pinfunction "P$1_TP") (pintype "bidirectional"))
    )
    (net (code "51") (name "Net-(IC32-A1)") (class "Default")
      (node (ref "IC32") (pin "3") (pinfunction "A1_3") (pintype "bidirectional"))
      (node (ref "IC36") (pin "22") (pinfunction "GPA7_22") (pintype "bidirectional"))
    )
    (net (code "52") (name "Net-(IC32-A2)") (class "Default")
      (node (ref "IC32") (pin "4") (pinfunction "A2_4") (pintype "bidirectional"))
      (node (ref "IC36") (pin "21") (pinfunction "GPA6_21") (pintype "bidirectional"))
    )
    (net (code "53") (name "Net-(IC32-A3)") (class "Default")
      (node (ref "IC32") (pin "5") (pinfunction "A3_5") (pintype "bidirectional"))
      (node (ref "IC36") (pin "20") (pinfunction "GPA5_20") (pintype "bidirectional"))
    )
    (net (code "54") (name "Net-(IC32-A4)") (class "Default")
      (node (ref "IC32") (pin "6") (pinfunction "A4_6") (pintype "bidirectional"))
      (node (ref "IC36") (pin "19") (pinfunction "GPA4_19") (pintype "bidirectional"))
    )
    (net (code "55") (name "Net-(IC32-A5)") (class "Default")
      (node (ref "IC32") (pin "7") (pinfunction "A5_7") (pintype "bidirectional"))
      (node (ref "IC36") (pin "18") (pinfunction "GPA3_18") (pintype "bidirectional"))
    )
    (net (code "56") (name "Net-(IC32-A6)") (class "Default")
      (node (ref "IC32") (pin "8") (pinfunction "A6_8") (pintype "bidirectional"))
      (node (ref "IC36") (pin "17") (pinfunction "GPA2_17") (pintype "bidirectional"))
    )
    (net (code "57") (name "Net-(IC32-A7)") (class "Default")
      (node (ref "IC32") (pin "9") (pinfunction "A7_9") (pintype "bidirectional"))
      (node (ref "IC36") (pin "16") (pinfunction "GPA1_16") (pintype "bidirectional"))
    )
    (net (code "58") (name "Net-(IC32-A8)") (class "Default")
      (node (ref "IC32") (pin "10") (pinfunction "A8_10") (pintype "bidirectional"))
      (node (ref "IC36") (pin "15") (pinfunction "GPA0_15") (pintype "bidirectional"))
    )
    (net (code "59") (name "Net-(IC32-B1)") (class "Default")
      (node (ref "IC32") (pin "18") (pinfunction "B1_18") (pintype "bidirectional"))
      (node (ref "R119") (pin "1") (pinfunction "1_1") (pintype "passive"))
    )
    (net (code "60") (name "Net-(IC32-B2)") (class "Default")
      (node (ref "IC32") (pin "17") (pinfunction "B2_17") (pintype "bidirectional"))
      (node (ref "R119") (pin "2") (pinfunction "2_2") (pintype "passive"))
    )
    (net (code "61") (name "Net-(IC32-B3)") (class "Default")
      (node (ref "IC32") (pin "16") (pinfunction "B3_16") (pintype "bidirectional"))
      (node (ref "R119") (pin "3") (pinfunction "3_3") (pintype "passive"))
    )
    (net (code "62") (name "Net-(IC32-B4)") (class "Default")
      (node (ref "IC32") (pin "15") (pinfunction "B4_15") (pintype "bidirectional"))
      (node (ref "R119") (pin "4") (pinfunction "4_4") (pintype "passive"))
    )
    (net (code "63") (name "Net-(IC32-B5)") (class "Default")
      (node (ref "IC32") (pin "14") (pinfunction "B5_14") (pintype "bidirectional"))
      (node (ref "R120") (pin "1") (pinfunction "1_1") (pintype "passive"))
    )
    (net (code "64") (name "Net-(IC32-B6)") (class "Default")
      (node (ref "IC32") (pin "13") (pinfunction "B6_13") (pintype "bidirectional"))
      (node (ref "R120") (pin "2") (pinfunction "2_2") (pintype "passive"))
    )
    (net (code "65") (name "Net-(IC32-B7)") (class "Default")
      (node (ref "IC32") (pin "12") (pinfunction "B7_12") (pintype "bidirectional"))
      (node (ref "R120") (pin "3") (pinfunction "3_3") (pintype "passive"))
    )
    (net (code "66") (name "Net-(IC32-B8)") (class "Default")
      (node (ref "IC32") (pin "11") (pinfunction "B8_11") (pintype "bidirectional"))
      (node (ref "R120") (pin "4") (pinfunction "4_4") (pintype "passive"))
    )
    (net (code "67") (name "Net-(IC33-A1)") (class "Default")
      (node (ref "IC33") (pin "3") (pinfunction "A1_3") (pintype "bidirectional"))
      (node (ref "IC36") (pin "7") (pinfunction "GPB7_7") (pintype "bidirectional"))
    )
    (net (code "68") (name "Net-(IC33-A2)") (class "Default")
      (node (ref "IC33") (pin "4") (pinfunction "A2_4") (pintype "bidirectional"))
      (node (ref "IC36") (pin "6") (pinfunction "GPB6_6") (pintype "bidirectional"))
    )
    (net (code "69") (name "Net-(IC33-A3)") (class "Default")
      (node (ref "IC33") (pin "5") (pinfunction "A3_5") (pintype "bidirectional"))
      (node (ref "IC36") (pin "5") (pinfunction "GPB5_5") (pintype "bidirectional"))
    )
    (net (code "70") (name "Net-(IC33-A4)") (class "Default")
      (node (ref "IC33") (pin "6") (pinfunction "A4_6") (pintype "bidirectional"))
      (node (ref "IC36") (pin "4") (pinfunction "GPB4_4") (pintype "bidirectional"))
    )
    (net (code "71") (name "Net-(IC33-A5)") (class "Default")
      (node (ref "IC33") (pin "7") (pinfunction "A5_7") (pintype "bidirectional"))
      (node (ref "IC36") (pin "3") (pinfunction "GPB3_3") (pintype "bidirectional"))
    )
    (net (code "72") (name "Net-(IC33-A6)") (class "Default")
      (node (ref "IC33") (pin "8") (pinfunction "A6_8") (pintype "bidirectional"))
      (node (ref "IC36") (pin "2") (pinfunction "GPB2_2") (pintype "bidirectional"))
    )
    (net (code "73") (name "Net-(IC33-A7)") (class "Default")
      (node (ref "IC33") (pin "9") (pinfunction "A7_9") (pintype "bidirectional"))
      (node (ref "IC36") (pin "1") (pinfunction "GPB1_1") (pintype "bidirectional"))
    )
    (net (code "74") (name "Net-(IC33-A8)") (class "Default")
      (node (ref "IC33") (pin "10") (pinfunction "A8_10") (pintype "bidirectional"))
      (node (ref "IC36") (pin "24") (pinfunction "GPB0_24") (pintype "bidirectional"))
    )
    (net (code "75") (name "Net-(IC33-B1)") (class "Default")
      (node (ref "IC33") (pin "18") (pinfunction "B1_18") (pintype "bidirectional"))
      (node (ref "R121") (pin "1") (pinfunction "1_1") (pintype "passive"))
    )
    (net (code "76") (name "Net-(IC33-B2)") (class "Default")
      (node (ref "IC33") (pin "17") (pinfunction "B2_17") (pintype "bidirectional"))
      (node (ref "R121") (pin "2") (pinfunction "2_2") (pintype "passive"))
    )
    (net (code "77") (name "Net-(IC33-B3)") (class "Default")
      (node (ref "IC33") (pin "16") (pinfunction "B3_16") (pintype "bidirectional"))
      (node (ref "R121") (pin "3") (pinfunction "3_3") (pintype "passive"))
    )
    (net (code "78") (name "Net-(IC33-B4)") (class "Default")
      (node (ref "IC33") (pin "15") (pinfunction "B4_15") (pintype "bidirectional"))
      (node (ref "R121") (pin "4") (pinfunction "4_4") (pintype "passive"))
    )
    (net (code "79") (name "Net-(IC33-B5)") (class "Default")
      (node (ref "IC33") (pin "14") (pinfunction "B5_14") (pintype "bidirectional"))
      (node (ref "R122") (pin "1") (pinfunction "1_1") (pintype "passive"))
    )
    (net (code "80") (name "Net-(IC33-B6)") (class "Default")
      (node (ref "IC33") (pin "13") (pinfunction "B6_13") (pintype "bidirectional"))
      (node (ref "R122") (pin "2") (pinfunction "2_2") (pintype "passive"))
    )
    (net (code "81") (name "Net-(IC33-B7)") (class "Default")
      (node (ref "IC33") (pin "12") (pinfunction "B7_12") (pintype "bidirectional"))
      (node (ref "R122") (pin "3") (pinfunction "3_3") (pintype "passive"))
    )
    (net (code "82") (name "Net-(IC33-B8)") (class "Default")
      (node (ref "IC33") (pin "11") (pinfunction "B8_11") (pintype "bidirectional"))
      (node (ref "R122") (pin "4") (pinfunction "4_4") (pintype "passive"))
    )
    (net (code "83") (name "Net-(IC34-A1)") (class "Default")
      (node (ref "IC34") (pin "3") (pinfunction "A1_3") (pintype "bidirectional"))
      (node (ref "IC37") (pin "22") (pinfunction "GPA7_22") (pintype "bidirectional"))
    )
    (net (code "84") (name "Net-(IC34-A2)") (class "Default")
      (node (ref "IC34") (pin "4") (pinfunction "A2_4") (pintype "bidirectional"))
      (node (ref "IC37") (pin "21") (pinfunction "GPA6_21") (pintype "bidirectional"))
    )
    (net (code "85") (name "Net-(IC34-A3)") (class "Default")
      (node (ref "IC34") (pin "5") (pinfunction "A3_5") (pintype "bidirectional"))
      (node (ref "IC37") (pin "20") (pinfunction "GPA5_20") (pintype "bidirectional"))
    )
    (net (code "86") (name "Net-(IC34-A4)") (class "Default")
      (node (ref "IC34") (pin "6") (pinfunction "A4_6") (pintype "bidirectional"))
      (node (ref "IC37") (pin "19") (pinfunction "GPA4_19") (pintype "bidirectional"))
    )
    (net (code "87") (name "Net-(IC34-A5)") (class "Default")
      (node (ref "IC34") (pin "7") (pinfunction "A5_7") (pintype "bidirectional"))
      (node (ref "IC37") (pin "18") (pinfunction "GPA3_18") (pintype "bidirectional"))
    )
    (net (code "88") (name "Net-(IC34-A6)") (class "Default")
      (node (ref "IC34") (pin "8") (pinfunction "A6_8") (pintype "bidirectional"))
      (node (ref "IC37") (pin "17") (pinfunction "GPA2_17") (pintype "bidirectional"))
    )
    (net (code "89") (name "Net-(IC34-A7)") (class "Default")
      (node (ref "IC34") (pin "9") (pinfunction "A7_9") (pintype "bidirectional"))
      (node (ref "IC37") (pin "16") (pinfunction "GPA1_16") (pintype "bidirectional"))
    )
    (net (code "90") (name "Net-(IC34-A8)") (class "Default")
      (node (ref "IC34") (pin "10") (pinfunction "A8_10") (pintype "bidirectional"))
      (node (ref "IC37") (pin "15") (pinfunction "GPA0_15") (pintype "bidirectional"))
    )
    (net (code "91") (name "Net-(IC34-B1)") (class "Default")
      (node (ref "IC34") (pin "18") (pinfunction "B1_18") (pintype "bidirectional"))
      (node (ref "R123") (pin "1") (pinfunction "1_1") (pintype "passive"))
    )
    (net (code "92") (name "Net-(IC34-B2)") (class "Default")
      (node (ref "IC34") (pin "17") (pinfunction "B2_17") (pintype "bidirectional"))
      (node (ref "R123") (pin "2") (pinfunction "2_2") (pintype "passive"))
    )
    (net (code "93") (name "Net-(IC34-B3)") (class "Default")
      (node (ref "IC34") (pin "16") (pinfunction "B3_16") (pintype "bidirectional"))
      (node (ref "R123") (pin "3") (pinfunction "3_3") (pintype "passive"))
    )
    (net (code "94") (name "Net-(IC34-B4)") (class "Default")
      (node (ref "IC34") (pin "15") (pinfunction "B4_15") (pintype "bidirectional"))
      (node (ref "R123") (pin "4") (pinfunction "4_4") (pintype "passive"))
    )
    (net (code "95") (name "Net-(IC34-B5)") (class "Default")
      (node (ref "IC34") (pin "14") (pinfunction "B5_14") (pintype "bidirectional"))
      (node (ref "R124") (pin "1") (pinfunction "1_1") (pintype "passive"))
    )
    (net (code "96") (name "Net-(IC34-B6)") (class "Default")
      (node (ref "IC34") (pin "13") (pinfunction "B6_13") (pintype "bidirectional"))
      (node (ref "R124") (pin "2") (pinfunction "2_2") (pintype "passive"))
    )
    (net (code "97") (name "Net-(IC34-B7)") (class "Default")
      (node (ref "IC34") (pin "12") (pinfunction "B7_12") (pintype "bidirectional"))
      (node (ref "R124") (pin "3") (pinfunction "3_3") (pintype "passive"))
    )
    (net (code "98") (name "Net-(IC34-B8)") (class "Default")
      (node (ref "IC34") (pin "11") (pinfunction "B8_11") (pintype "bidirectional"))
      (node (ref "R124") (pin "4") (pinfunction "4_4") (pintype "passive"))
    )
    (net (code "99") (name "Net-(IC35-A1)") (class "Default")
      (node (ref "IC35") (pin "3") (pinfunction "A1_3") (pintype "bidirectional"))
      (node (ref "IC37") (pin "7") (pinfunction "GPB7_7") (pintype "bidirectional"))
    )
    (net (code "100") (name "Net-(IC35-A2)") (class "Default")
      (node (ref "IC35") (pin "4") (pinfunction "A2_4") (pintype "bidirectional"))
      (node (ref "IC37") (pin "6") (pinfunction "GPB6_6") (pintype "bidirectional"))
    )
    (net (code "101") (name "Net-(IC35-A3)") (class "Default")
      (node (ref "IC35") (pin "5") (pinfunction "A3_5") (pintype "bidirectional"))
      (node (ref "IC37") (pin "5") (pinfunction "GPB5_5") (pintype "bidirectional"))
    )
    (net (code "102") (name "Net-(IC35-A4)") (class "Default")
      (node (ref "IC35") (pin "6") (pinfunction "A4_6") (pintype "bidirectional"))
      (node (ref "IC37") (pin "4") (pinfunction "GPB4_4") (pintype "bidirectional"))
    )
    (net (code "103") (name "Net-(IC35-A5)") (class "Default")
      (node (ref "IC35") (pin "7") (pinfunction "A5_7") (pintype "bidirectional"))
      (node (ref "IC37") (pin "3") (pinfunction "GPB3_3") (pintype "bidirectional"))
    )
    (net (code "104") (name "Net-(IC35-A6)") (class "Default")
      (node (ref "IC35") (pin "8") (pinfunction "A6_8") (pintype "bidirectional"))
      (node (ref "IC37") (pin "2") (pinfunction "GPB2_2") (pintype "bidirectional"))
    )
    (net (code "105") (name "Net-(IC35-A7)") (class "Default")
      (node (ref "IC35") (pin "9") (pinfunction "A7_9") (pintype "bidirectional"))
      (node (ref "IC37") (pin "1") (pinfunction "GPB1_1") (pintype "bidirectional"))
    )
    (net (code "106") (name "Net-(IC35-A8)") (class "Default")
      (node (ref "IC35") (pin "10") (pinfunction "A8_10") (pintype "bidirectional"))
      (node (ref "IC37") (pin "24") (pinfunction "GPB0_24") (pintype "bidirectional"))
    )
    (net (code "107") (name "Net-(IC35-B1)") (class "Default")
      (node (ref "IC35") (pin "18") (pinfunction "B1_18") (pintype "bidirectional"))
      (node (ref "R125") (pin "1") (pinfunction "1_1") (pintype "passive"))
    )
    (net (code "108") (name "Net-(IC35-B2)") (class "Default")
      (node (ref "IC35") (pin "17") (pinfunction "B2_17") (pintype "bidirectional"))
      (node (ref "R125") (pin "2") (pinfunction "2_2") (pintype "passive"))
    )
    (net (code "109") (name "Net-(IC35-B3)") (class "Default")
      (node (ref "IC35") (pin "16") (pinfunction "B3_16") (pintype "bidirectional"))
      (node (ref "R125") (pin "3") (pinfunction "3_3") (pintype "passive"))
    )
    (net (code "110") (name "Net-(IC35-B4)") (class "Default")
      (node (ref "IC35") (pin "15") (pinfunction "B4_15") (pintype "bidirectional"))
      (node (ref "R125") (pin "4") (pinfunction "4_4") (pintype "passive"))
    )
    (net (code "111") (name "Net-(IC35-B5)") (class "Default")
      (node (ref "IC35") (pin "14") (pinfunction "B5_14") (pintype "bidirectional"))
      (node (ref "R126") (pin "1") (pinfunction "1_1") (pintype "passive"))
    )
    (net (code "112") (name "Net-(IC35-B6)") (class "Default")
      (node (ref "IC35") (pin "13") (pinfunction "B6_13") (pintype "bidirectional"))
      (node (ref "R126") (pin "2") (pinfunction "2_2") (pintype "passive"))
    )
    (net (code "113") (name "Net-(IC35-B7)") (class "Default")
      (node (ref "IC35") (pin "12") (pinfunction "B7_12") (pintype "bidirectional"))
      (node (ref "R126") (pin "3") (pinfunction "3_3") (pintype "passive"))
    )
    (net (code "114") (name "Net-(IC35-B8)") (class "Default")
      (node (ref "IC35") (pin "11") (pinfunction "B8_11") (pintype "bidirectional"))
      (node (ref "R126") (pin "4") (pinfunction "4_4") (pintype "passive"))
    )
    (net (code "115") (name "Net-(X1-OUT)") (class "Default")
      (node (ref "C2") (pin "1") (pinfunction "1_1") (pintype "passive"))
      (node (ref "R1") (pin "1") (pinfunction "1_1") (pintype "passive"))
      (node (ref "R9") (pin "2") (pinfunction "2_2") (pintype "passive"))
      (node (ref "X1") (pin "3") (pinfunction "OUT_3") (pintype "output"))
    )
    (net (code "116") (name "Net-(X3A-1)") (class "Default")
      (node (ref "JP-3V3-1") (pin "2") (pinfunction "2_2") (pintype "passive"))
      (node (ref "X3") (pin "A1") (pinfunction "1_A1") (pintype "passive"))
    )
    (net (code "117") (name "Net-(X3B-1)") (class "Default")
      (node (ref "JP-3V3-2") (pin "2") (pinfunction "2_2") (pintype "passive"))
      (node (ref "X3") (pin "B1") (pinfunction "1_B1") (pintype "passive"))
    )
    (net (code "118") (name "QSPI_SCLK") (class "Default")
      (node (ref "IC2") (pin "52") (pinfunction "QSPI_SCLK_52") (pintype "bidirectional"))
      (node (ref "IC4") (pin "6") (pinfunction "CLK_6") (pintype "bidirectional"))
    )
    (net (code "119") (name "QSPI_SD0") (class "Default")
      (node (ref "IC2") (pin "53") (pinfunction "QSPI_SD0_53") (pintype "bidirectional"))
      (node (ref "IC4") (pin "5") (pinfunction "DI/IO0_5") (pintype "bidirectional"))
    )
    (net (code "120") (name "QSPI_SD1") (class "Default")
      (node (ref "IC2") (pin "55") (pinfunction "QSPI_SD1_55") (pintype "bidirectional"))
      (node (ref "IC4") (pin "2") (pinfunction "DO/IO1_2") (pintype "bidirectional"))
    )
    (net (code "121") (name "QSPI_SD2") (class "Default")
      (node (ref "IC2") (pin "54") (pinfunction "QSPI_SD2_54") (pintype "bidirectional"))
      (node (ref "IC4") (pin "3") (pinfunction "~{WP}/IO2_3") (pintype "bidirectional"))
    )
    (net (code "122") (name "QSPI_SD3") (class "Default")
      (node (ref "IC2") (pin "51") (pinfunction "QSPI_SD3_51") (pintype "bidirectional"))
      (node (ref "IC4") (pin "7") (pinfunction "~{HOLD}/IO3_7") (pintype "bidirectional"))
    )
    (net (code "123") (name "RP2040_RST") (class "Default")
      (node (ref "IC2") (pin "26") (pinfunction "RUN_26") (pintype "bidirectional"))
      (node (ref "R75") (pin "2") (pinfunction "2_2") (pintype "passive"))
      (node (ref "RESET") (pin "1") (pinfunction "P_1") (pintype "passive"))
      (node (ref "X3") (pin "B18") (pinfunction "18_B18") (pintype "passive"))
    )
    (net (code "124") (name "RP_XI") (class "Default")
      (node (ref "C1") (pin "1") (pinfunction "1_1") (pintype "passive"))
      (node (ref "IC2") (pin "20") (pinfunction "XIN_20") (pintype "bidirectional"))
      (node (ref "R9") (pin "1") (pinfunction "1_1") (pintype "passive"))
      (node (ref "X1") (pin "1") (pinfunction "CON_1") (pintype "input"))
    )
    (net (code "125") (name "RP_XO") (class "Default")
      (node (ref "IC2") (pin "21") (pinfunction "XOUT_21") (pintype "bidirectional"))
      (node (ref "R1") (pin "2") (pinfunction "2_2") (pintype "passive"))
    )
    (net (code "126") (name "SPI0_CS0") (class "Default")
      (node (ref "CS0") (pin "TP") (pinfunction "P$1_TP") (pintype "bidirectional"))
      (node (ref "IC2") (pin "7") (pinfunction "GPIO5_7") (pintype "bidirectional"))
      (node (ref "IC36") (pin "9") (pinfunction "~{CS}_9") (pintype "input"))
      (node (ref "X3") (pin "A2") (pinfunction "2_A2") (pintype "passive"))
    )
    (net (code "127") (name "SPI0_CS1") (class "Default")
      (node (ref "CS1") (pin "TP") (pinfunction "P$1_TP") (pintype "bidirectional"))
      (node (ref "IC2") (pin "8") (pinfunction "GPIO6_8") (pintype "bidirectional"))
      (node (ref "IC37") (pin "9") (pinfunction "~{CS}_9") (pintype "input"))
      (node (ref "X3") (pin "A3") (pinfunction "3_A3") (pintype "passive"))
    )
    (net (code "128") (name "SPI0_MISO") (class "Default")
      (node (ref "IC2") (pin "6") (pinfunction "GPIO4_6") (pintype "bidirectional"))
      (node (ref "IC36") (pin "12") (pinfunction "SO_12") (pintype "output"))
      (node (ref "IC37") (pin "12") (pinfunction "SO_12") (pintype "output"))
      (node (ref "MISO") (pin "TP") (pinfunction "P$1_TP") (pintype "bidirectional"))
      (node (ref "X3") (pin "A7") (pinfunction "7_A7") (pintype "passive"))
      (node (ref "X3") (pin "B7") (pinfunction "7_B7") (pintype "passive"))
    )
    (net (code "129") (name "SPI0_MOSI") (class "Default")
      (node (ref "IC2") (pin "5") (pinfunction "GPIO3_5") (pintype "bidirectional"))
      (node (ref "IC36") (pin "11") (pinfunction "SI_11") (pintype "input"))
      (node (ref "IC37") (pin "11") (pinfunction "SI_11") (pintype "input"))
      (node (ref "MOSI") (pin "TP") (pinfunction "P$1_TP") (pintype "bidirectional"))
      (node (ref "X3") (pin "A6") (pinfunction "6_A6") (pintype "passive"))
      (node (ref "X3") (pin "B6") (pinfunction "6_B6") (pintype "passive"))
    )
    (net (code "130") (name "SPI0_SCK") (class "Default")
      (node (ref "IC2") (pin "4") (pinfunction "GPIO2_4") (pintype "bidirectional"))
      (node (ref "IC36") (pin "10") (pinfunction "SCK_10") (pintype "input"))
      (node (ref "IC37") (pin "10") (pinfunction "SCK_10") (pintype "input"))
      (node (ref "SCK") (pin "TP") (pinfunction "P$1_TP") (pintype "bidirectional"))
      (node (ref "X3") (pin "A5") (pinfunction "5_A5") (pintype "passive"))
      (node (ref "X3") (pin "B5") (pinfunction "5_B5") (pintype "passive"))
    )
    (net (code "131") (name "SPI1_CS") (class "Default")
      (node (ref "IC2") (pin "16") (pinfunction "GPIO13_16") (pintype "bidirectional"))
      (node (ref "X3") (pin "A29") (pinfunction "29_A29") (pintype "passive"))
      (node (ref "X3") (pin "B29") (pinfunction "29_B29") (pintype "passive"))
    )
    (net (code "132") (name "SPI1_MISO") (class "Default")
      (node (ref "IC2") (pin "15") (pinfunction "GPIO12_15") (pintype "bidirectional"))
      (node (ref "X3") (pin "A26") (pinfunction "26_A26") (pintype "passive"))
      (node (ref "X3") (pin "B26") (pinfunction "26_B26") (pintype "passive"))
    )
    (net (code "133") (name "SPI1_MOSI") (class "Default")
      (node (ref "IC2") (pin "14") (pinfunction "GPIO11_14") (pintype "bidirectional"))
      (node (ref "X3") (pin "A27") (pinfunction "27_A27") (pintype "passive"))
      (node (ref "X3") (pin "B27") (pinfunction "27_B27") (pintype "passive"))
    )
    (net (code "134") (name "SPI1_SCK") (class "Default")
      (node (ref "IC2") (pin "13") (pinfunction "GPIO10_13") (pintype "bidirectional"))
      (node (ref "X3") (pin "A28") (pinfunction "28_A28") (pintype "passive"))
      (node (ref "X3") (pin "B28") (pinfunction "28_B28") (pintype "passive"))
    )
    (net (code "135") (name "SWCLK") (class "Default")
      (node (ref "DBG2") (pin "1") (pinfunction "P$1_1") (pintype "bidirectional"))
      (node (ref "IC2") (pin "24") (pinfunction "SWCLK_24") (pintype "bidirectional"))
      (node (ref "X3") (pin "B23") (pinfunction "23_B23") (pintype "passive"))
    )
    (net (code "136") (name "SWDIO") (class "Default")
      (node (ref "DBG2") (pin "3") (pinfunction "P$3_3") (pintype "bidirectional"))
      (node (ref "IC2") (pin "25") (pinfunction "SWDIO_25") (pintype "bidirectional"))
      (node (ref "X3") (pin "B24") (pinfunction "24_B24") (pintype "passive"))
    )
    (net (code "137") (name "UART0_RX") (class "Default")
      (node (ref "DBG1") (pin "1") (pinfunction "P$1_1") (pintype "bidirectional"))
      (node (ref "IC2") (pin "2") (pinfunction "GPIO0_2") (pintype "bidirectional"))
      (node (ref "X3") (pin "B20") (pinfunction "20_B20") (pintype "passive"))
    )
    (net (code "138") (name "UART0_TX") (class "Default")
      (node (ref "DBG1") (pin "3") (pinfunction "P$3_3") (pintype "bidirectional"))
      (node (ref "IC2") (pin "3") (pinfunction "GPIO1_3") (pintype "bidirectional"))
      (node (ref "X3") (pin "B21") (pinfunction "21_B21") (pintype "passive"))
    )
    (net (code "139") (name "USBD_N") (class "Default")
      (node (ref "ESD1") (pin "3") (pinfunction "C2_3") (pintype "bidirectional"))
      (node (ref "R6") (pin "1") (pinfunction "1_1") (pintype "passive"))
      (node (ref "USBC") (pin "A7") (pinfunction "D-1_A7") (pintype "passive"))
      (node (ref "USBC") (pin "B7") (pinfunction "D-2_B7") (pintype "passive"))
    )
    (net (code "140") (name "USBD_P") (class "Default")
      (node (ref "ESD1") (pin "2") (pinfunction "C1_2") (pintype "bidirectional"))
      (node (ref "R7") (pin "1") (pinfunction "1_1") (pintype "passive"))
      (node (ref "USBC") (pin "A6") (pinfunction "D+1_A6") (pintype "passive"))
      (node (ref "USBC") (pin "B6") (pinfunction "D+2_B6") (pintype "passive"))
    )
    (net (code "141") (name "USB_BOOT") (class "Default")
      (node (ref "R4") (pin "1") (pinfunction "1_1") (pintype "passive"))
      (node (ref "USB_BOOT") (pin "1") (pinfunction "P_1") (pintype "passive"))
    )
    (net (code "142") (name "USB_SHIELD") (class "Default")
      (node (ref "C115") (pin "1") (pinfunction "1_1") (pintype "passive"))
      (node (ref "R68") (pin "1") (pinfunction "1_1") (pintype "passive"))
      (node (ref "USBC") (pin "S1") (pinfunction "SHIELD_S1") (pintype "passive"))
      (node (ref "USBC") (pin "S2") (pinfunction "SHIELD_S2") (pintype "passive"))
      (node (ref "USBC") (pin "S3") (pinfunction "SHIELD_S3") (pintype "passive"))
      (node (ref "USBC") (pin "S4") (pinfunction "SHIELD_S4") (pintype "passive"))
    )
    (net (code "143") (name "VBUS") (class "Default")
      (node (ref "C78") (pin "1") (pinfunction "1_1") (pintype "passive"))
      (node (ref "C79") (pin "1") (pinfunction "1_1") (pintype "passive"))
      (node (ref "D1") (pin "A") (pinfunction "A_A") (pintype "passive"))
      (node (ref "ESD1") (pin "4") (pinfunction "C3_4") (pintype "bidirectional"))
      (node (ref "R5") (pin "1") (pinfunction "1_1") (pintype "passive"))
      (node (ref "R63") (pin "1") (pinfunction "1_1") (pintype "passive"))
      (node (ref "USBC") (pin "A4") (pinfunction "VBUS_A4") (pintype "passive"))
      (node (ref "USBC") (pin "A9") (pinfunction "VBUS1_A9") (pintype "passive"))
      (node (ref "USBC") (pin "B4") (pinfunction "VBUS3_B4") (pintype "passive"))
      (node (ref "USBC") (pin "B9") (pinfunction "VBUS2_B9") (pintype "passive"))
      (node (ref "VBUS") (pin "TP") (pinfunction "P$1_TP") (pintype "bidirectional"))
    )
    (net (code "144") (name "V_OUT_REF") (class "Default")
      (node (ref "C153") (pin "1") (pinfunction "1_1") (pintype "passive"))
      (node (ref "C154") (pin "1") (pinfunction "1_1") (pintype "passive"))
      (node (ref "C157") (pin "1") (pinfunction "1_1") (pintype "passive"))
      (node (ref "C158") (pin "1") (pinfunction "1_1") (pintype "passive"))
      (node (ref "C161") (pin "1") (pinfunction "1_1") (pintype "passive"))
      (node (ref "C162") (pin "1") (pinfunction "1_1") (pintype "passive"))
      (node (ref "C165") (pin "1") (pinfunction "1_1") (pintype "passive"))
      (node (ref "C166") (pin "1") (pinfunction "1_1") (pintype "passive"))
      (node (ref "DIO_VREF") (pin "TP") (pinfunction "P$1_TP") (pintype "bidirectional"))
      (node (ref "IC32") (pin "19") (pinfunction "VREF_B_19") (pintype "power_in"))
      (node (ref "IC33") (pin "19") (pinfunction "VREF_B_19") (pintype "power_in"))
      (node (ref "IC34") (pin "19") (pinfunction "VREF_B_19") (pintype "power_in"))
      (node (ref "IC35") (pin "19") (pinfunction "VREF_B_19") (pintype "power_in"))
      (node (ref "IC38") (pin "2") (pinfunction "1B_2") (pintype "bidirectional"))
      (node (ref "IC38") (pin "6") (pinfunction "2B_6") (pintype "bidirectional"))
      (node (ref "R10") (pin "1") (pinfunction "1_1") (pintype "passive"))
      (node (ref "R11") (pin "1") (pinfunction "1_1") (pintype "passive"))
      (node (ref "R127") (pin "1") (pinfunction "1_1") (pintype "passive"))
      (node (ref "R22") (pin "1") (pinfunction "1_1") (pintype "passive"))
      (node (ref "R8") (pin "1") (pinfunction "1_1") (pintype "passive"))
    )
    (net (code "145") (name "unconnected-(IC1-NC-Pad4)") (class "Default")
      (node (ref "IC1") (pin "4") (pinfunction "NC_4") (pintype "bidirectional"))
    )
    (net (code "146") (name "unconnected-(IC2-GPIO14-Pad17)") (class "Default")
      (node (ref "IC2") (pin "17") (pinfunction "GPIO14_17") (pintype "bidirectional"))
    )
    (net (code "147") (name "unconnected-(IC2-GPIO15-Pad18)") (class "Default")
      (node (ref "IC2") (pin "18") (pinfunction "GPIO15_18") (pintype "bidirectional"))
    )
    (net (code "148") (name "unconnected-(IC2-GPIO16-Pad27)") (class "Default")
      (node (ref "IC2") (pin "27") (pinfunction "GPIO16_27") (pintype "bidirectional"))
    )
    (net (code "149") (name "unconnected-(IC2-GPIO17-Pad28)") (class "Default")
      (node (ref "IC2") (pin "28") (pinfunction "GPIO17_28") (pintype "bidirectional"))
    )
    (net (code "150") (name "unconnected-(IC2-GPIO18-Pad29)") (class "Default")
      (node (ref "IC2") (pin "29") (pinfunction "GPIO18_29") (pintype "bidirectional"))
    )
    (net (code "151") (name "unconnected-(IC2-GPIO19-Pad30)") (class "Default")
      (node (ref "IC2") (pin "30") (pinfunction "GPIO19_30") (pintype "bidirectional"))
    )
    (net (code "152") (name "unconnected-(IC2-GPIO20-Pad31)") (class "Default")
      (node (ref "IC2") (pin "31") (pinfunction "GPIO20_31") (pintype "bidirectional"))
    )
    (net (code "153") (name "unconnected-(IC2-GPIO21-Pad32)") (class "Default")
      (node (ref "IC2") (pin "32") (pinfunction "GPIO21_32") (pintype "bidirectional"))
    )
    (net (code "154") (name "unconnected-(IC2-GPIO22-Pad34)") (class "Default")
      (node (ref "IC2") (pin "34") (pinfunction "GPIO22_34") (pintype "bidirectional"))
    )
    (net (code "155") (name "unconnected-(IC2-GPIO23-Pad35)") (class "Default")
      (node (ref "IC2") (pin "35") (pinfunction "GPIO23_35") (pintype "bidirectional"))
    )
    (net (code "156") (name "unconnected-(IC2-GPIO24-Pad36)") (class "Default")
      (node (ref "IC2") (pin "36") (pinfunction "GPIO24_36") (pintype "bidirectional"))
    )
    (net (code "157") (name "unconnected-(IC2-GPIO25-Pad37)") (class "Default")
      (node (ref "IC2") (pin "37") (pinfunction "GPIO25_37") (pintype "bidirectional"))
    )
    (net (code "158") (name "unconnected-(IC36-INTA-Pad14)") (class "Default")
      (node (ref "IC36") (pin "14") (pinfunction "INTA_14") (pintype "output"))
    )
    (net (code "159") (name "unconnected-(IC37-INTA-Pad14)") (class "Default")
      (node (ref "IC37") (pin "14") (pinfunction "INTA_14") (pintype "output"))
    )
    (net (code "160") (name "unconnected-(USBC-SBU1-PadA8)") (class "Default")
      (node (ref "USBC") (pin "A8") (pinfunction "SBU1_A8") (pintype "passive"))
    )
    (net (code "161") (name "unconnected-(USBC-SBU2-PadB8)") (class "Default")
      (node (ref "USBC") (pin "B8") (pinfunction "SBU2_B8") (pintype "passive"))
    )
    (net (code "162") (name "unconnected-(X3A-4-PadA4)") (class "Default")
      (node (ref "X3") (pin "A4") (pinfunction "4_A4") (pintype "passive"))
    )
    (net (code "163") (name "unconnected-(X3A-17-PadA17)") (class "Default")
      (node (ref "X3") (pin "A17") (pinfunction "17_A17") (pintype "passive"))
    )
    (net (code "164") (name "unconnected-(X3A-18-PadA18)") (class "Default")
      (node (ref "X3") (pin "A18") (pinfunction "18_A18") (pintype "passive"))
    )
    (net (code "165") (name "unconnected-(X3A-19-PadA19)") (class "Default")
      (node (ref "X3") (pin "A19") (pinfunction "19_A19") (pintype "passive"))
    )
    (net (code "166") (name "unconnected-(X3A-20-PadA20)") (class "Default")
      (node (ref "X3") (pin "A20") (pinfunction "20_A20") (pintype "passive"))
    )
    (net (code "167") (name "unconnected-(X3A-21-PadA21)") (class "Default")
      (node (ref "X3") (pin "A21") (pinfunction "21_A21") (pintype "passive"))
    )
    (net (code "168") (name "unconnected-(X3A-22-PadA22)") (class "Default")
      (node (ref "X3") (pin "A22") (pinfunction "22_A22") (pintype "passive"))
    )
    (net (code "169") (name "unconnected-(X3A-23-PadA23)") (class "Default")
      (node (ref "X3") (pin "A23") (pinfunction "23_A23") (pintype "passive"))
    )
    (net (code "170") (name "unconnected-(X3A-24-PadA24)") (class "Default")
      (node (ref "X3") (pin "A24") (pinfunction "24_A24") (pintype "passive"))
    )
    (net (code "171") (name "unconnected-(X3B-2-PadB2)") (class "Default")
      (node (ref "X3") (pin "B2") (pinfunction "2_B2") (pintype "passive"))
    )
    (net (code "172") (name "unconnected-(X3B-3-PadB3)") (class "Default")
      (node (ref "X3") (pin "B3") (pinfunction "3_B3") (pintype "passive"))
    )
    (net (code "173") (name "unconnected-(X3B-4-PadB4)") (class "Default")
      (node (ref "X3") (pin "B4") (pinfunction "4_B4") (pintype "passive"))
    )
    (net (code "174") (name "unconnected-(X3B-11-PadB11)") (class "Default")
      (node (ref "X3") (pin "B11") (pinfunction "11_B11") (pintype "passive"))
    )
    (net (code "175") (name "unconnected-(X3B-12-PadB12)") (class "Default")
      (node (ref "X3") (pin "B12") (pinfunction "12_B12") (pintype "passive"))
    )
    (net (code "176") (name "unconnected-(X3B-13-PadB13)") (class "Default")
      (node (ref "X3") (pin "B13") (pinfunction "13_B13") (pintype "passive"))
    )
    (net (code "177") (name "unconnected-(X3B-17-PadB17)") (class "Default")
      (node (ref "X3") (pin "B17") (pinfunction "17_B17") (pintype "passive"))
    )
    (net (code "178") (name "~{DIO_LEVEL_SELECT}") (class "Default")
      (node (ref "IC38") (pin "3") (pinfunction "2C_3") (pintype "input"))
      (node (ref "IC39") (pin "4") (pinfunction "OUT_4") (pintype "bidirectional"))
    )
    (net (code "179") (name "~{QSPI_SS}") (class "Default")
      (node (ref "IC2") (pin "56") (pinfunction "QSPI_SS_N_56") (pintype "bidirectional"))
      (node (ref "IC4") (pin "1") (pinfunction "~{CS}_1") (pintype "bidirectional"))
      (node (ref "R3") (pin "1") (pinfunction "1_1") (pintype "passive"))
      (node (ref "R4") (pin "2") (pinfunction "2_2") (pintype "passive"))
    )
  )
)
